# 10_RF_1.net
KiCad netlist of a schematic drawn in Altium Designer
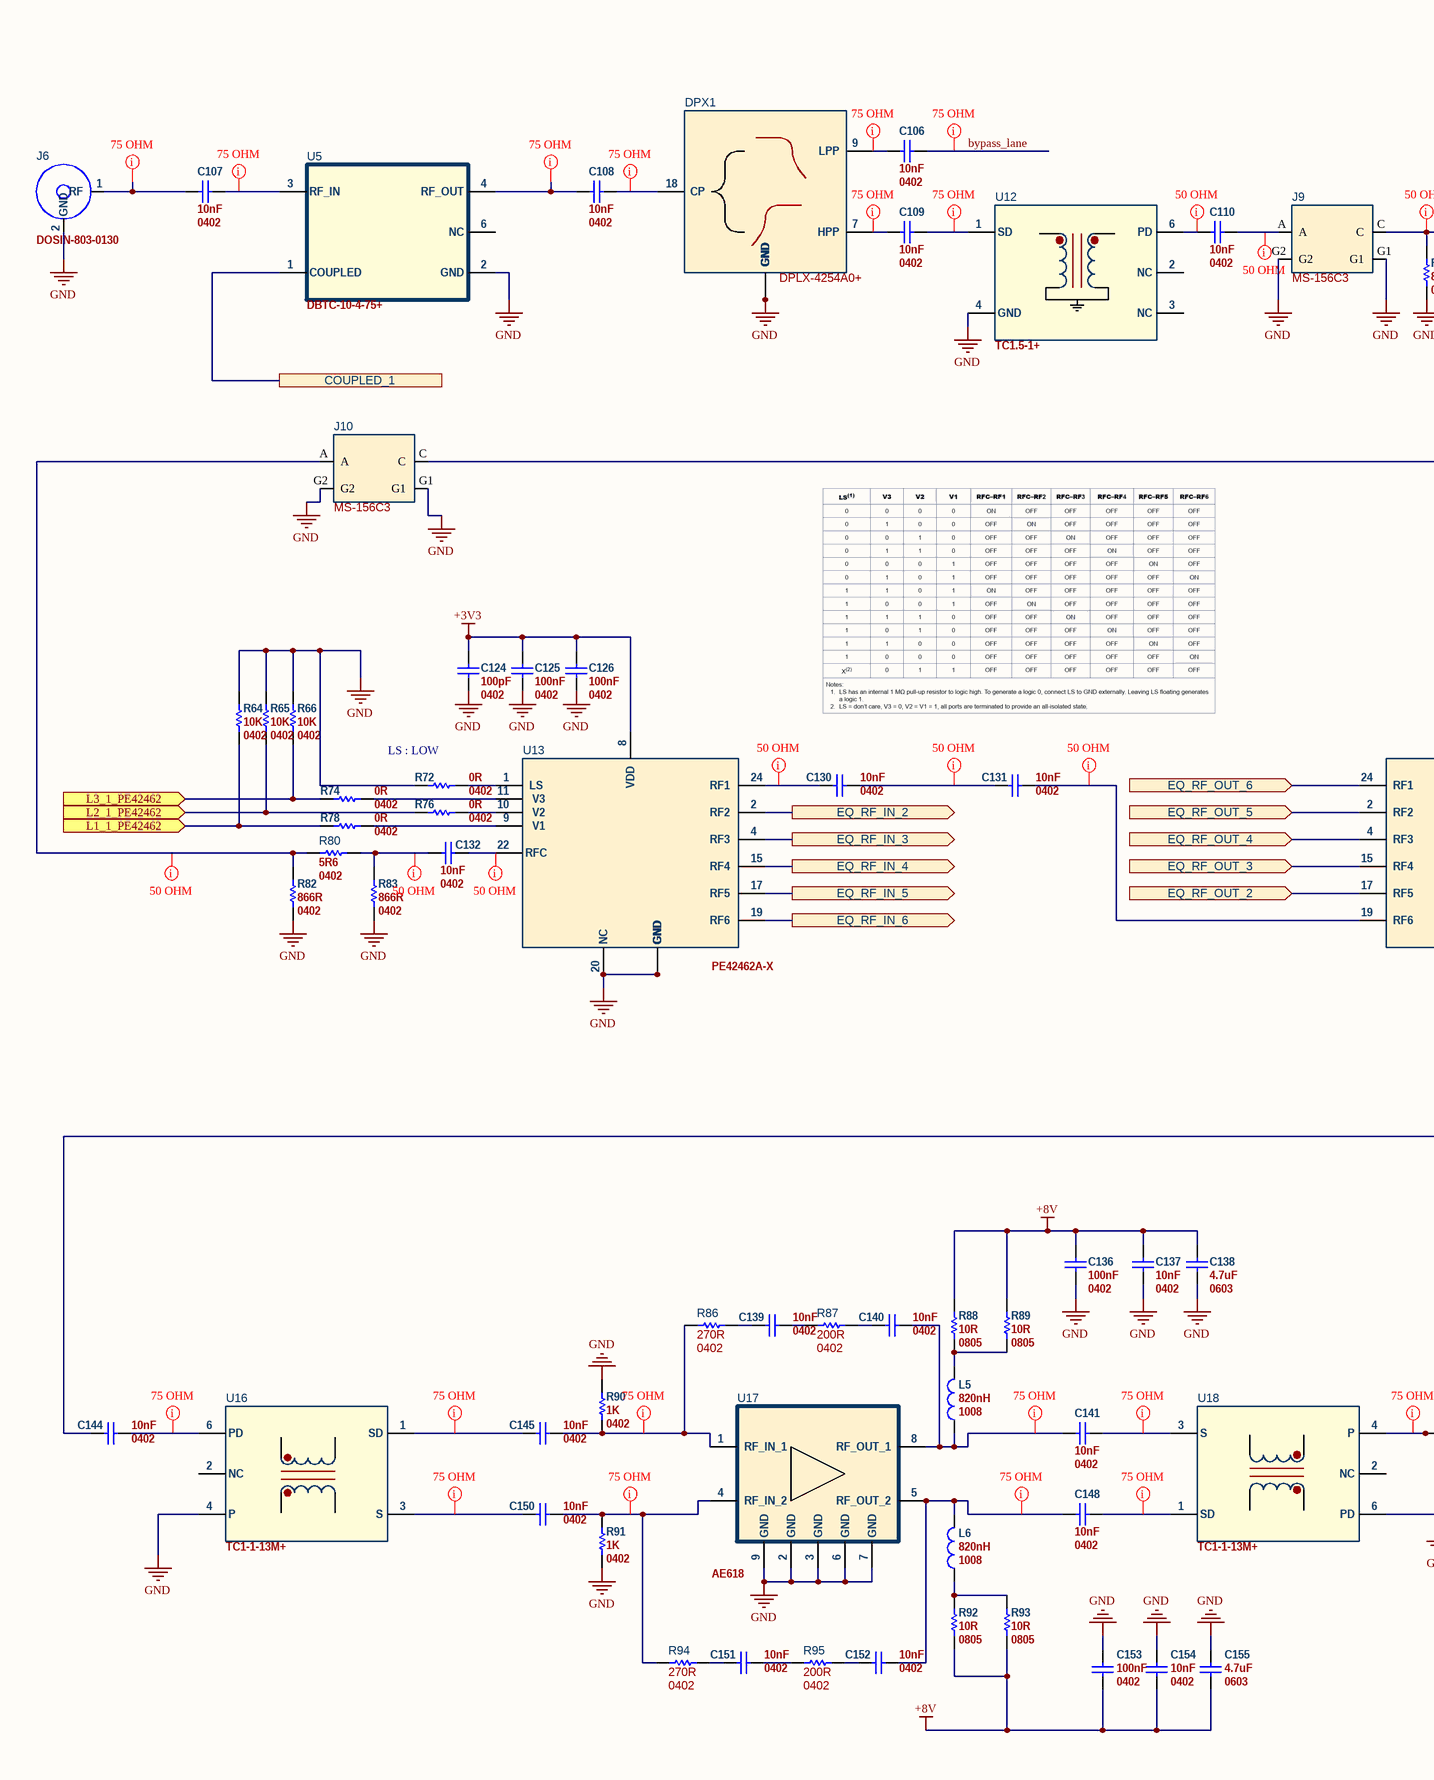
[diagram p0: 10_RF_1.SchDoc, left]
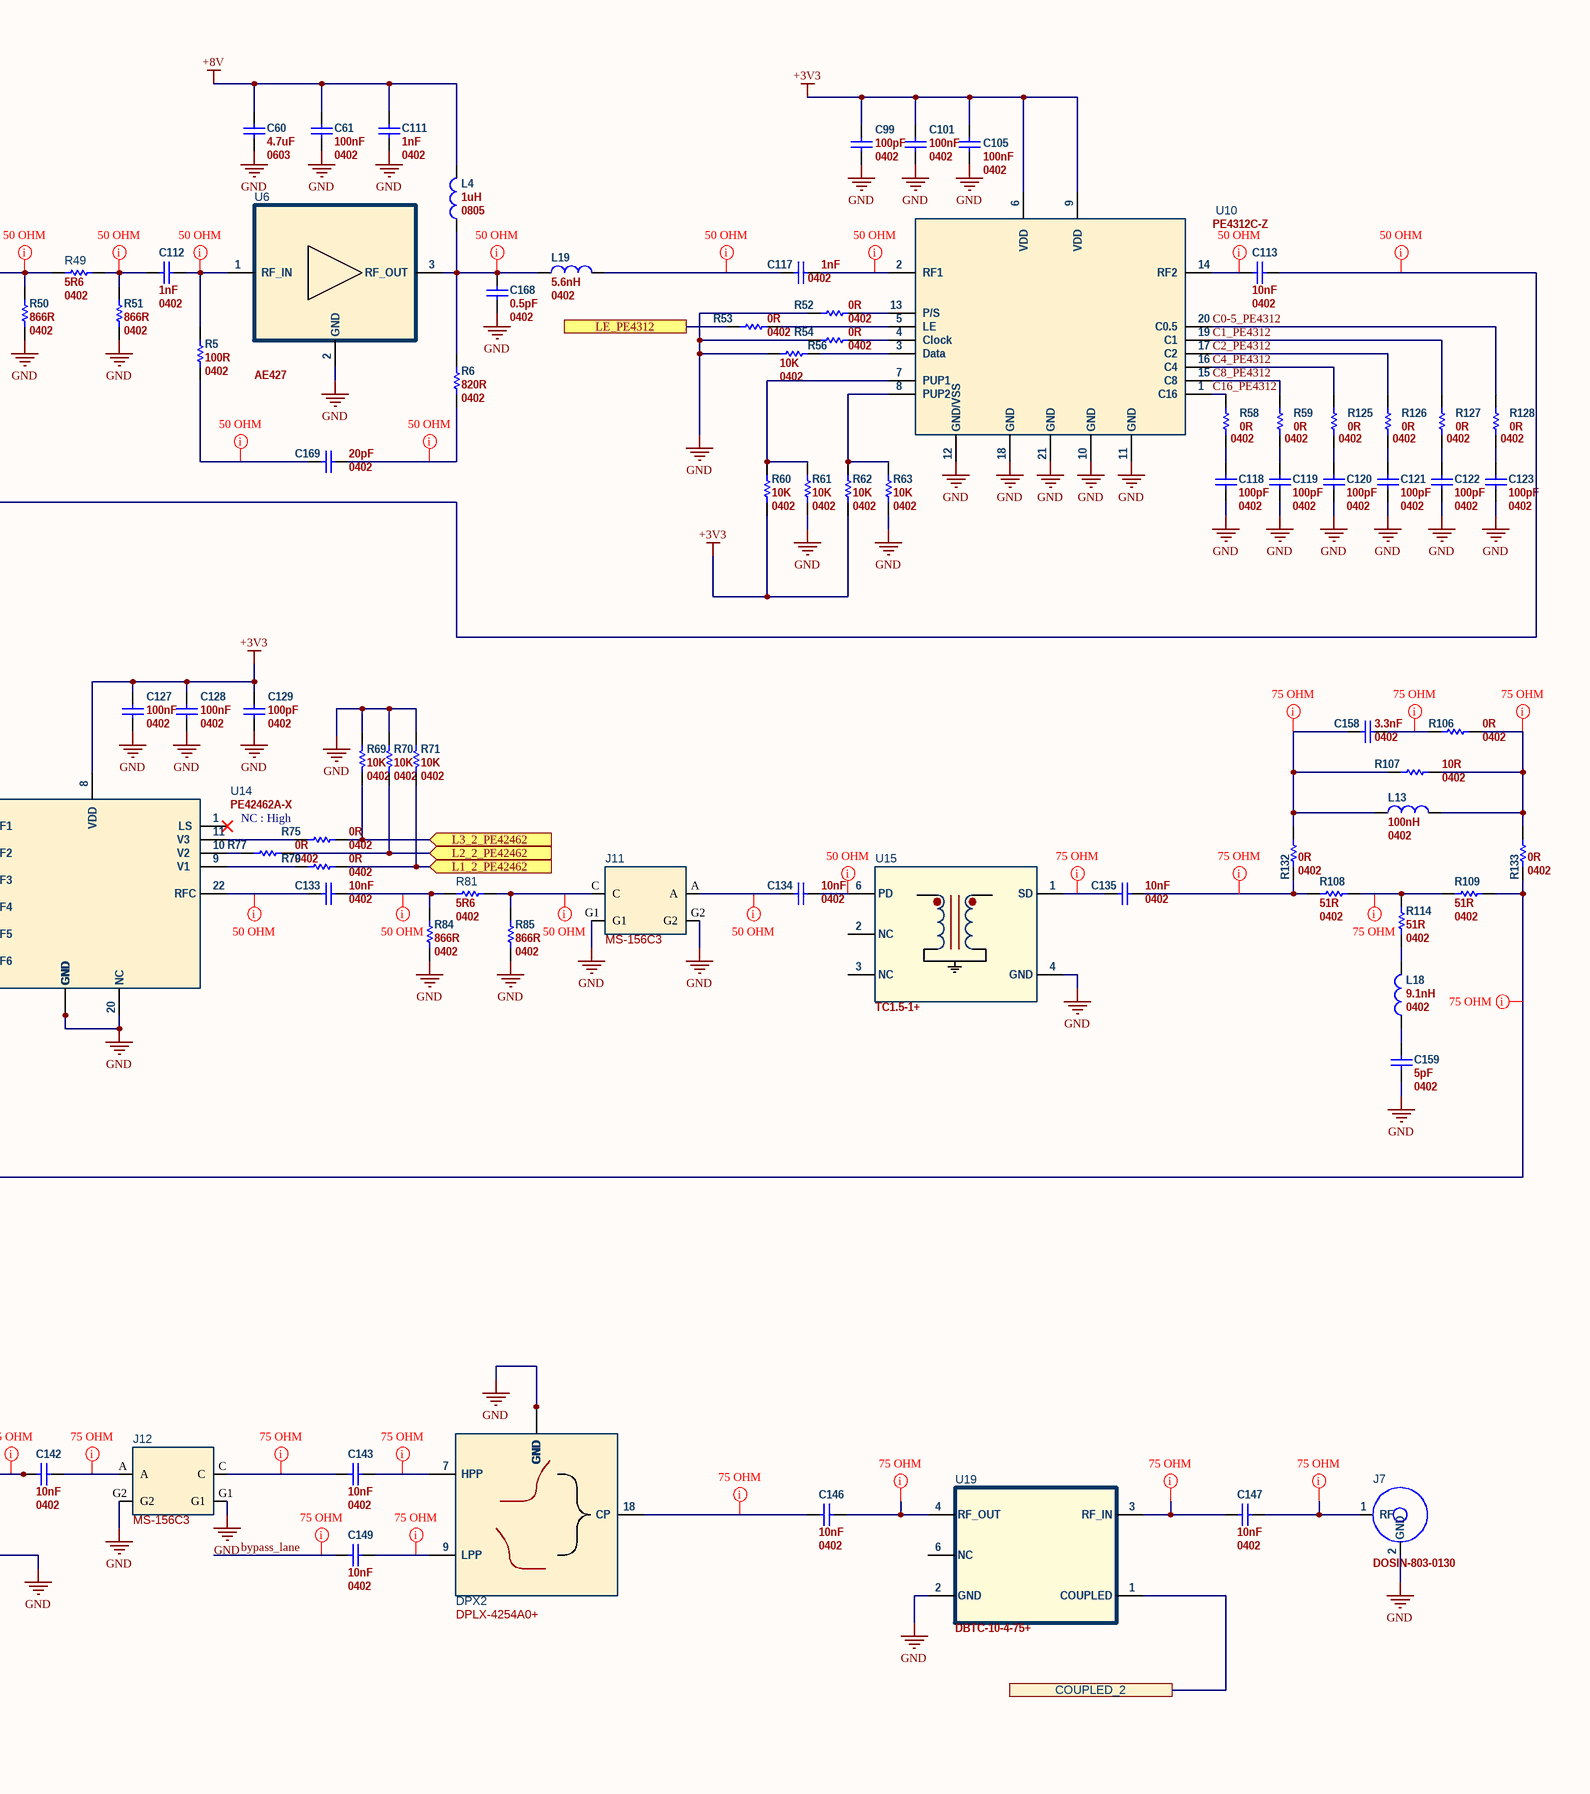
[diagram p1: 10_RF_1.SchDoc, right]

(export (version "E")
  (design (tool "Eeschema 10.0.6"))
  (components
    (comp (ref "C60")
      (value "4.7uF")
      (footprint "DISCRETE:CAP_0603_N")
      (description "CAP CER 4.7uF 16V X7R 0603 ±10%")
      (fields
        (field (name "TOLERANCE") "±10%")
        (field (name "PACKAGE") "0603")
        (field (name "Comment") "C 0603 16V X7R - 4.7uF")
        (field (name "COMPONENTLINK2URL") "D:\\SAVRONIK_SVN\\Donanım\\trunk\\ALTIUM\\Central Library\\Datasheets\\Capacitor\\GRM188Z71C475KE21-01A_Datasheet.pdf")
      )
      (libsource (lib "CAPACITOR") (part "C 0603 16V X7R - 4.7uF"))
    )
    (comp (ref "C61")
      (value "100nF")
      (footprint "DISCRETE:CAP_0402_N")
      (description "CAP CER 100nF 50V X7R 0402 ±10%")
      (fields
        (field (name "TOLERANCE") "±10%")
        (field (name "PACKAGE") "0402")
        (field (name "Comment") "C 0402 50V X7R - 100nF")
        (field (name "COMPONENTLINK2URL") "D:\\SAVRONIK_SVN\\Donanım\\trunk\\ALTIUM\\Central Library\\Datasheets\\Capacitor\\CGA2B3X7R1H104K050BB_Datasheet.pdf")
      )
      (libsource (lib "CAPACITOR") (part "C 0402 50V X7R - 100nF"))
    )
    (comp (ref "C99")
      (value "100pF")
      (footprint "DISCRETE:CAP_0402_N")
      (description "CAP CER 100pF 50V NP0 0402 ±1%")
      (fields
        (field (name "TOLERANCE") "±1%")
        (field (name "PACKAGE") "0402")
        (field (name "Comment") "C 0402 50V NP0 - 100pF")
      )
      (libsource (lib "CAPACITOR") (part "C 0402 50V NP0 - 100pF"))
    )
    (comp (ref "C101")
      (value "100nF")
      (footprint "DISCRETE:CAP_0402_N")
      (description "CAP CER 100nF 50V X7R 0402 ±10%")
      (fields
        (field (name "TOLERANCE") "±10%")
        (field (name "PACKAGE") "0402")
        (field (name "Comment") "C 0402 50V X7R - 100nF")
        (field (name "COMPONENTLINK2URL") "D:\\SAVRONIK_SVN\\Donanım\\trunk\\ALTIUM\\Central Library\\Datasheets\\Capacitor\\CGA2B3X7R1H104K050BB_Datasheet.pdf")
      )
      (libsource (lib "CAPACITOR") (part "C 0402 50V X7R - 100nF"))
    )
    (comp (ref "C105")
      (value "100nF")
      (footprint "DISCRETE:CAP_0402_N")
      (description "CAP CER 100nF 50V X7R 0402 ±10%")
      (fields
        (field (name "TOLERANCE") "±10%")
        (field (name "PACKAGE") "0402")
        (field (name "Comment") "C 0402 50V X7R - 100nF")
        (field (name "COMPONENTLINK2URL") "D:\\SAVRONIK_SVN\\Donanım\\trunk\\ALTIUM\\Central Library\\Datasheets\\Capacitor\\CGA2B3X7R1H104K050BB_Datasheet.pdf")
      )
      (libsource (lib "CAPACITOR") (part "C 0402 50V X7R - 100nF"))
    )
    (comp (ref "C106")
      (value "10nF")
      (footprint "DISCRETE:CAP_0402_N")
      (description "CAP CER 10nF 50V X7R 0402 ±10%")
      (fields
        (field (name "TOLERANCE") "±10%")
        (field (name "PACKAGE") "0402")
        (field (name "Comment") "C 0402 50V X7R - 10nF")
      )
      (libsource (lib "CAPACITOR") (part "C 0402 50V X7R - 10nF"))
    )
    (comp (ref "C107")
      (value "10nF")
      (footprint "DISCRETE:CAP_0402_N")
      (description "CAP CER 10nF 50V X7R 0402 ±10%")
      (fields
        (field (name "TOLERANCE") "±10%")
        (field (name "PACKAGE") "0402")
        (field (name "Comment") "C 0402 50V X7R - 10nF")
      )
      (libsource (lib "CAPACITOR") (part "C 0402 50V X7R - 10nF"))
    )
    (comp (ref "C108")
      (value "10nF")
      (footprint "DISCRETE:CAP_0402_N")
      (description "CAP CER 10nF 50V X7R 0402 ±10%")
      (fields
        (field (name "TOLERANCE") "±10%")
        (field (name "PACKAGE") "0402")
        (field (name "Comment") "C 0402 50V X7R - 10nF")
      )
      (libsource (lib "CAPACITOR") (part "C 0402 50V X7R - 10nF"))
    )
    (comp (ref "C109")
      (value "10nF")
      (footprint "DISCRETE:CAP_0402_N")
      (description "CAP CER 10nF 50V X7R 0402 ±10%")
      (fields
        (field (name "TOLERANCE") "±10%")
        (field (name "PACKAGE") "0402")
        (field (name "Comment") "C 0402 50V X7R - 10nF")
      )
      (libsource (lib "CAPACITOR") (part "C 0402 50V X7R - 10nF"))
    )
    (comp (ref "C110")
      (value "10nF")
      (footprint "DISCRETE:CAP_0402_N")
      (description "CAP CER 10nF 50V X7R 0402 ±10%")
      (fields
        (field (name "TOLERANCE") "±10%")
        (field (name "PACKAGE") "0402")
        (field (name "Comment") "C 0402 50V X7R - 10nF")
      )
      (libsource (lib "CAPACITOR") (part "C 0402 50V X7R - 10nF"))
    )
    (comp (ref "C111")
      (value "1nF")
      (footprint "DISCRETE:CAP_0402_N")
      (description "CAP CER 1nF 50V X7R 0402 ±10%")
      (fields
        (field (name "TOLERANCE") "±10%")
        (field (name "PACKAGE") "0402")
        (field (name "Comment") "C 0402 50V X7R - 1nF")
      )
      (libsource (lib "CAPACITOR") (part "C 0402 50V X7R - 1nF"))
    )
    (comp (ref "C112")
      (value "1nF")
      (footprint "DISCRETE:CAP_0402_N")
      (description "CAP CER 1nF 50V X7R 0402 ±10%")
      (fields
        (field (name "TOLERANCE") "±10%")
        (field (name "PACKAGE") "0402")
        (field (name "Comment") "C 0402 50V X7R - 1nF")
      )
      (libsource (lib "CAPACITOR") (part "C 0402 50V X7R - 1nF"))
    )
    (comp (ref "C113")
      (value "10nF")
      (footprint "DISCRETE:CAP_0402_N")
      (description "CAP CER 10nF 50V X7R 0402 ±10%")
      (fields
        (field (name "TOLERANCE") "±10%")
        (field (name "PACKAGE") "0402")
        (field (name "Comment") "C 0402 50V X7R - 10nF")
      )
      (libsource (lib "CAPACITOR") (part "C 0402 50V X7R - 10nF"))
    )
    (comp (ref "C117")
      (value "1nF")
      (footprint "DISCRETE:CAP_0402_N")
      (description "CAP CER 1nF 50V X7R 0402 ±10%")
      (fields
        (field (name "TOLERANCE") "±10%")
        (field (name "PACKAGE") "0402")
        (field (name "Comment") "C 0402 50V X7R - 1nF")
      )
      (libsource (lib "CAPACITOR") (part "C 0402 50V X7R - 1nF"))
    )
    (comp (ref "C118")
      (value "100pF")
      (footprint "DISCRETE:CAP_0402_N")
      (description "CAP CER 100pF 50V NP0 0402 ±1%")
      (fields
        (field (name "TOLERANCE") "±1%")
        (field (name "PACKAGE") "0402")
        (field (name "Comment") "C 0402 50V NP0 - 100pF")
      )
      (libsource (lib "CAPACITOR") (part "C 0402 50V NP0 - 100pF"))
    )
    (comp (ref "C119")
      (value "100pF")
      (footprint "DISCRETE:CAP_0402_N")
      (description "CAP CER 100pF 50V NP0 0402 ±1%")
      (fields
        (field (name "TOLERANCE") "±1%")
        (field (name "PACKAGE") "0402")
        (field (name "Comment") "C 0402 50V NP0 - 100pF")
      )
      (libsource (lib "CAPACITOR") (part "C 0402 50V NP0 - 100pF"))
    )
    (comp (ref "C120")
      (value "100pF")
      (footprint "DISCRETE:CAP_0402_N")
      (description "CAP CER 100pF 50V NP0 0402 ±1%")
      (fields
        (field (name "TOLERANCE") "±1%")
        (field (name "PACKAGE") "0402")
        (field (name "Comment") "C 0402 50V NP0 - 100pF")
      )
      (libsource (lib "CAPACITOR") (part "C 0402 50V NP0 - 100pF"))
    )
    (comp (ref "C121")
      (value "100pF")
      (footprint "DISCRETE:CAP_0402_N")
      (description "CAP CER 100pF 50V NP0 0402 ±1%")
      (fields
        (field (name "TOLERANCE") "±1%")
        (field (name "PACKAGE") "0402")
        (field (name "Comment") "C 0402 50V NP0 - 100pF")
      )
      (libsource (lib "CAPACITOR") (part "C 0402 50V NP0 - 100pF"))
    )
    (comp (ref "C122")
      (value "100pF")
      (footprint "DISCRETE:CAP_0402_N")
      (description "CAP CER 100pF 50V NP0 0402 ±1%")
      (fields
        (field (name "TOLERANCE") "±1%")
        (field (name "PACKAGE") "0402")
        (field (name "Comment") "C 0402 50V NP0 - 100pF")
      )
      (libsource (lib "CAPACITOR") (part "C 0402 50V NP0 - 100pF"))
    )
    (comp (ref "C123")
      (value "100pF")
      (footprint "DISCRETE:CAP_0402_N")
      (description "CAP CER 100pF 50V NP0 0402 ±1%")
      (fields
        (field (name "TOLERANCE") "±1%")
        (field (name "PACKAGE") "0402")
        (field (name "Comment") "C 0402 50V NP0 - 100pF")
      )
      (libsource (lib "CAPACITOR") (part "C 0402 50V NP0 - 100pF"))
    )
    (comp (ref "C124")
      (value "100pF")
      (footprint "DISCRETE:CAP_0402_N")
      (description "CAP CER 100pF 50V NP0 0402 ±1%")
      (fields
        (field (name "TOLERANCE") "±1%")
        (field (name "PACKAGE") "0402")
        (field (name "Comment") "C 0402 50V NP0 - 100pF")
      )
      (libsource (lib "CAPACITOR") (part "C 0402 50V NP0 - 100pF"))
    )
    (comp (ref "C125")
      (value "100nF")
      (footprint "DISCRETE:CAP_0402_N")
      (description "CAP CER 100nF 50V X7R 0402 ±10%")
      (fields
        (field (name "TOLERANCE") "±10%")
        (field (name "PACKAGE") "0402")
        (field (name "Comment") "C 0402 50V X7R - 100nF")
        (field (name "COMPONENTLINK2URL") "D:\\SAVRONIK_SVN\\Donanım\\trunk\\ALTIUM\\Central Library\\Datasheets\\Capacitor\\CGA2B3X7R1H104K050BB_Datasheet.pdf")
      )
      (libsource (lib "CAPACITOR") (part "C 0402 50V X7R - 100nF"))
    )
    (comp (ref "C126")
      (value "100nF")
      (footprint "DISCRETE:CAP_0402_N")
      (description "CAP CER 100nF 50V X7R 0402 ±10%")
      (fields
        (field (name "TOLERANCE") "±10%")
        (field (name "PACKAGE") "0402")
        (field (name "Comment") "C 0402 50V X7R - 100nF")
        (field (name "COMPONENTLINK2URL") "D:\\SAVRONIK_SVN\\Donanım\\trunk\\ALTIUM\\Central Library\\Datasheets\\Capacitor\\CGA2B3X7R1H104K050BB_Datasheet.pdf")
      )
      (libsource (lib "CAPACITOR") (part "C 0402 50V X7R - 100nF"))
    )
    (comp (ref "C127")
      (value "100nF")
      (footprint "DISCRETE:CAP_0402_N")
      (description "CAP CER 100nF 50V X7R 0402 ±10%")
      (fields
        (field (name "TOLERANCE") "±10%")
        (field (name "PACKAGE") "0402")
        (field (name "Comment") "C 0402 50V X7R - 100nF")
        (field (name "COMPONENTLINK2URL") "D:\\SAVRONIK_SVN\\Donanım\\trunk\\ALTIUM\\Central Library\\Datasheets\\Capacitor\\CGA2B3X7R1H104K050BB_Datasheet.pdf")
      )
      (libsource (lib "CAPACITOR") (part "C 0402 50V X7R - 100nF"))
    )
    (comp (ref "C128")
      (value "100nF")
      (footprint "DISCRETE:CAP_0402_N")
      (description "CAP CER 100nF 50V X7R 0402 ±10%")
      (fields
        (field (name "TOLERANCE") "±10%")
        (field (name "PACKAGE") "0402")
        (field (name "Comment") "C 0402 50V X7R - 100nF")
        (field (name "COMPONENTLINK2URL") "D:\\SAVRONIK_SVN\\Donanım\\trunk\\ALTIUM\\Central Library\\Datasheets\\Capacitor\\CGA2B3X7R1H104K050BB_Datasheet.pdf")
      )
      (libsource (lib "CAPACITOR") (part "C 0402 50V X7R - 100nF"))
    )
    (comp (ref "C129")
      (value "100pF")
      (footprint "DISCRETE:CAP_0402_N")
      (description "CAP CER 100pF 50V NP0 0402 ±1%")
      (fields
        (field (name "TOLERANCE") "±1%")
        (field (name "PACKAGE") "0402")
        (field (name "Comment") "C 0402 50V NP0 - 100pF")
      )
      (libsource (lib "CAPACITOR") (part "C 0402 50V NP0 - 100pF"))
    )
    (comp (ref "C130")
      (value "10nF")
      (footprint "DISCRETE:CAP_0402_N")
      (description "CAP CER 10nF 50V X7R 0402 ±10%")
      (fields
        (field (name "TOLERANCE") "±10%")
        (field (name "PACKAGE") "0402")
        (field (name "Comment") "C 0402 50V X7R - 10nF")
      )
      (libsource (lib "CAPACITOR") (part "C 0402 50V X7R - 10nF"))
    )
    (comp (ref "C131")
      (value "10nF")
      (footprint "DISCRETE:CAP_0402_N")
      (description "CAP CER 10nF 50V X7R 0402 ±10%")
      (fields
        (field (name "TOLERANCE") "±10%")
        (field (name "PACKAGE") "0402")
        (field (name "Comment") "C 0402 50V X7R - 10nF")
      )
      (libsource (lib "CAPACITOR") (part "C 0402 50V X7R - 10nF"))
    )
    (comp (ref "C132")
      (value "10nF")
      (footprint "DISCRETE:CAP_0402_N")
      (description "CAP CER 10nF 50V X7R 0402 ±10%")
      (fields
        (field (name "TOLERANCE") "±10%")
        (field (name "PACKAGE") "0402")
        (field (name "Comment") "C 0402 50V X7R - 10nF")
      )
      (libsource (lib "CAPACITOR") (part "C 0402 50V X7R - 10nF"))
    )
    (comp (ref "C133")
      (value "10nF")
      (footprint "DISCRETE:CAP_0402_N")
      (description "CAP CER 10nF 50V X7R 0402 ±10%")
      (fields
        (field (name "TOLERANCE") "±10%")
        (field (name "PACKAGE") "0402")
        (field (name "Comment") "C 0402 50V X7R - 10nF")
      )
      (libsource (lib "CAPACITOR") (part "C 0402 50V X7R - 10nF"))
    )
    (comp (ref "C134")
      (value "10nF")
      (footprint "DISCRETE:CAP_0402_N")
      (description "CAP CER 10nF 50V X7R 0402 ±10%")
      (fields
        (field (name "TOLERANCE") "±10%")
        (field (name "PACKAGE") "0402")
        (field (name "Comment") "C 0402 50V X7R - 10nF")
      )
      (libsource (lib "CAPACITOR") (part "C 0402 50V X7R - 10nF"))
    )
    (comp (ref "C135")
      (value "10nF")
      (footprint "DISCRETE:CAP_0402_N")
      (description "CAP CER 10nF 50V X7R 0402 ±10%")
      (fields
        (field (name "TOLERANCE") "±10%")
        (field (name "PACKAGE") "0402")
        (field (name "Comment") "C 0402 50V X7R - 10nF")
      )
      (libsource (lib "CAPACITOR") (part "C 0402 50V X7R - 10nF"))
    )
    (comp (ref "C136")
      (value "100nF")
      (footprint "DISCRETE:CAP_0402_N")
      (description "CAP CER 100nF 50V X7R 0402 ±10%")
      (fields
        (field (name "TOLERANCE") "±10%")
        (field (name "PACKAGE") "0402")
        (field (name "Comment") "C 0402 50V X7R - 100nF")
        (field (name "COMPONENTLINK2URL") "D:\\SAVRONIK_SVN\\Donanım\\trunk\\ALTIUM\\Central Library\\Datasheets\\Capacitor\\CGA2B3X7R1H104K050BB_Datasheet.pdf")
      )
      (libsource (lib "CAPACITOR") (part "C 0402 50V X7R - 100nF"))
    )
    (comp (ref "C137")
      (value "10nF")
      (footprint "DISCRETE:CAP_0402_N")
      (description "CAP CER 10nF 50V X7R 0402 ±10%")
      (fields
        (field (name "TOLERANCE") "±10%")
        (field (name "PACKAGE") "0402")
        (field (name "Comment") "C 0402 50V X7R - 10nF")
      )
      (libsource (lib "CAPACITOR") (part "C 0402 50V X7R - 10nF"))
    )
    (comp (ref "C138")
      (value "4.7uF")
      (footprint "DISCRETE:CAP_0603_N")
      (description "CAP CER 4.7uF 16V X7R 0603 ±10%")
      (fields
        (field (name "TOLERANCE") "±10%")
        (field (name "PACKAGE") "0603")
        (field (name "Comment") "C 0603 16V X7R - 4.7uF")
        (field (name "COMPONENTLINK2URL") "D:\\SAVRONIK_SVN\\Donanım\\trunk\\ALTIUM\\Central Library\\Datasheets\\Capacitor\\GRM188Z71C475KE21-01A_Datasheet.pdf")
      )
      (libsource (lib "CAPACITOR") (part "C 0603 16V X7R - 4.7uF"))
    )
    (comp (ref "C139")
      (value "10nF")
      (footprint "DISCRETE:CAP_0402_N")
      (description "CAP CER 10nF 50V X7R 0402 ±10%")
      (fields
        (field (name "TOLERANCE") "±10%")
        (field (name "PACKAGE") "0402")
        (field (name "Comment") "C 0402 50V X7R - 10nF")
      )
      (libsource (lib "CAPACITOR") (part "C 0402 50V X7R - 10nF"))
    )
    (comp (ref "C140")
      (value "10nF")
      (footprint "DISCRETE:CAP_0402_N")
      (description "CAP CER 10nF 50V X7R 0402 ±10%")
      (fields
        (field (name "TOLERANCE") "±10%")
        (field (name "PACKAGE") "0402")
        (field (name "Comment") "C 0402 50V X7R - 10nF")
      )
      (libsource (lib "CAPACITOR") (part "C 0402 50V X7R - 10nF"))
    )
    (comp (ref "C141")
      (value "10nF")
      (footprint "DISCRETE:CAP_0402_N")
      (description "CAP CER 10nF 50V X7R 0402 ±10%")
      (fields
        (field (name "TOLERANCE") "±10%")
        (field (name "PACKAGE") "0402")
        (field (name "Comment") "C 0402 50V X7R - 10nF")
      )
      (libsource (lib "CAPACITOR") (part "C 0402 50V X7R - 10nF"))
    )
    (comp (ref "C142")
      (value "10nF")
      (footprint "DISCRETE:CAP_0402_N")
      (description "CAP CER 10nF 50V X7R 0402 ±10%")
      (fields
        (field (name "TOLERANCE") "±10%")
        (field (name "PACKAGE") "0402")
        (field (name "Comment") "C 0402 50V X7R - 10nF")
      )
      (libsource (lib "CAPACITOR") (part "C 0402 50V X7R - 10nF"))
    )
    (comp (ref "C143")
      (value "10nF")
      (footprint "DISCRETE:CAP_0402_N")
      (description "CAP CER 10nF 50V X7R 0402 ±10%")
      (fields
        (field (name "TOLERANCE") "±10%")
        (field (name "PACKAGE") "0402")
        (field (name "Comment") "C 0402 50V X7R - 10nF")
      )
      (libsource (lib "CAPACITOR") (part "C 0402 50V X7R - 10nF"))
    )
    (comp (ref "C144")
      (value "10nF")
      (footprint "DISCRETE:CAP_0402_N")
      (description "CAP CER 10nF 50V X7R 0402 ±10%")
      (fields
        (field (name "TOLERANCE") "±10%")
        (field (name "PACKAGE") "0402")
        (field (name "Comment") "C 0402 50V X7R - 10nF")
      )
      (libsource (lib "CAPACITOR") (part "C 0402 50V X7R - 10nF"))
    )
    (comp (ref "C145")
      (value "10nF")
      (footprint "DISCRETE:CAP_0402_N")
      (description "CAP CER 10nF 50V X7R 0402 ±10%")
      (fields
        (field (name "TOLERANCE") "±10%")
        (field (name "PACKAGE") "0402")
        (field (name "Comment") "C 0402 50V X7R - 10nF")
      )
      (libsource (lib "CAPACITOR") (part "C 0402 50V X7R - 10nF"))
    )
    (comp (ref "C146")
      (value "10nF")
      (footprint "DISCRETE:CAP_0402_N")
      (description "CAP CER 10nF 50V X7R 0402 ±10%")
      (fields
        (field (name "TOLERANCE") "±10%")
        (field (name "PACKAGE") "0402")
        (field (name "Comment") "C 0402 50V X7R - 10nF")
      )
      (libsource (lib "CAPACITOR") (part "C 0402 50V X7R - 10nF"))
    )
    (comp (ref "C147")
      (value "10nF")
      (footprint "DISCRETE:CAP_0402_N")
      (description "CAP CER 10nF 50V X7R 0402 ±10%")
      (fields
        (field (name "TOLERANCE") "±10%")
        (field (name "PACKAGE") "0402")
        (field (name "Comment") "C 0402 50V X7R - 10nF")
      )
      (libsource (lib "CAPACITOR") (part "C 0402 50V X7R - 10nF"))
    )
    (comp (ref "C148")
      (value "10nF")
      (footprint "DISCRETE:CAP_0402_N")
      (description "CAP CER 10nF 50V X7R 0402 ±10%")
      (fields
        (field (name "TOLERANCE") "±10%")
        (field (name "PACKAGE") "0402")
        (field (name "Comment") "C 0402 50V X7R - 10nF")
      )
      (libsource (lib "CAPACITOR") (part "C 0402 50V X7R - 10nF"))
    )
    (comp (ref "C149")
      (value "10nF")
      (footprint "DISCRETE:CAP_0402_N")
      (description "CAP CER 10nF 50V X7R 0402 ±10%")
      (fields
        (field (name "TOLERANCE") "±10%")
        (field (name "PACKAGE") "0402")
        (field (name "Comment") "C 0402 50V X7R - 10nF")
      )
      (libsource (lib "CAPACITOR") (part "C 0402 50V X7R - 10nF"))
    )
    (comp (ref "C150")
      (value "10nF")
      (footprint "DISCRETE:CAP_0402_N")
      (description "CAP CER 10nF 50V X7R 0402 ±10%")
      (fields
        (field (name "TOLERANCE") "±10%")
        (field (name "PACKAGE") "0402")
        (field (name "Comment") "C 0402 50V X7R - 10nF")
      )
      (libsource (lib "CAPACITOR") (part "C 0402 50V X7R - 10nF"))
    )
    (comp (ref "C151")
      (value "10nF")
      (footprint "DISCRETE:CAP_0402_N")
      (description "CAP CER 10nF 50V X7R 0402 ±10%")
      (fields
        (field (name "TOLERANCE") "±10%")
        (field (name "PACKAGE") "0402")
        (field (name "Comment") "C 0402 50V X7R - 10nF")
      )
      (libsource (lib "CAPACITOR") (part "C 0402 50V X7R - 10nF"))
    )
    (comp (ref "C152")
      (value "10nF")
      (footprint "DISCRETE:CAP_0402_N")
      (description "CAP CER 10nF 50V X7R 0402 ±10%")
      (fields
        (field (name "TOLERANCE") "±10%")
        (field (name "PACKAGE") "0402")
        (field (name "Comment") "C 0402 50V X7R - 10nF")
      )
      (libsource (lib "CAPACITOR") (part "C 0402 50V X7R - 10nF"))
    )
    (comp (ref "C153")
      (value "100nF")
      (footprint "DISCRETE:CAP_0402_N")
      (description "CAP CER 100nF 50V X7R 0402 ±10%")
      (fields
        (field (name "TOLERANCE") "±10%")
        (field (name "PACKAGE") "0402")
        (field (name "Comment") "C 0402 50V X7R - 100nF")
        (field (name "COMPONENTLINK2URL") "D:\\SAVRONIK_SVN\\Donanım\\trunk\\ALTIUM\\Central Library\\Datasheets\\Capacitor\\CGA2B3X7R1H104K050BB_Datasheet.pdf")
      )
      (libsource (lib "CAPACITOR") (part "C 0402 50V X7R - 100nF"))
    )
    (comp (ref "C154")
      (value "10nF")
      (footprint "DISCRETE:CAP_0402_N")
      (description "CAP CER 10nF 50V X7R 0402 ±10%")
      (fields
        (field (name "TOLERANCE") "±10%")
        (field (name "PACKAGE") "0402")
        (field (name "Comment") "C 0402 50V X7R - 10nF")
      )
      (libsource (lib "CAPACITOR") (part "C 0402 50V X7R - 10nF"))
    )
    (comp (ref "C155")
      (value "4.7uF")
      (footprint "DISCRETE:CAP_0603_N")
      (description "CAP CER 4.7uF 16V X7R 0603 ±10%")
      (fields
        (field (name "TOLERANCE") "±10%")
        (field (name "PACKAGE") "0603")
        (field (name "Comment") "C 0603 16V X7R - 4.7uF")
        (field (name "COMPONENTLINK2URL") "D:\\SAVRONIK_SVN\\Donanım\\trunk\\ALTIUM\\Central Library\\Datasheets\\Capacitor\\GRM188Z71C475KE21-01A_Datasheet.pdf")
      )
      (libsource (lib "CAPACITOR") (part "C 0603 16V X7R - 4.7uF"))
    )
    (comp (ref "C158")
      (value "3.3nF")
      (footprint "DISCRETE:CAP_0402_N")
      (description "CAP CER 3.3nF 50V X7R 0402 ±5%")
      (fields
        (field (name "TOLERANCE") "±5%")
        (field (name "PACKAGE") "0402")
        (field (name "Comment") "C 0402 50V X7R - 3.3nF")
      )
      (libsource (lib "CAPACITOR") (part "C 0402 50V X7R - 3.3nF"))
    )
    (comp (ref "C159")
      (value "5pF")
      (footprint "DISCRETE:CAP_0402_N")
      (description "CAP CER 5pF 50V C0G/NP0 0402 ±0.1pF")
      (fields
        (field (name "TOLERANCE") "±0.1pF")
        (field (name "PACKAGE") "0402")
        (field (name "Comment") "C 0402 50V C0G/NP0 - 5pF")
      )
      (libsource (lib "CAPACITOR") (part "C 0402 50V C0G/NP0 - 5pF"))
    )
    (comp (ref "C168")
      (value "0.5pF")
      (footprint "DISCRETE:CAP_0402_N")
      (description "CAP CER 0.5pF 50V C0G/NP0 0402 ±0.1pF")
      (fields
        (field (name "TOLERANCE") "±0.1pF")
        (field (name "PACKAGE") "0402")
        (field (name "Comment") "C 0402 50V C0G/NP0 - 0.5pF")
      )
      (libsource (lib "CAPACITOR") (part "C 0402 50V C0G/NP0 - 0.5pF"))
    )
    (comp (ref "C169")
      (value "20pF")
      (footprint "DISCRETE:CAP_0402_N")
      (description "CAP CER 20pF 50V C0G/NP0 0402 ±1%")
      (fields
        (field (name "TOLERANCE") "±1%")
        (field (name "PACKAGE") "0402")
        (field (name "Comment") "C 0402 50V C0G/NP0 - 20pF")
      )
      (libsource (lib "CAPACITOR") (part "C 0402 50V C0G/NP0 - 20pF"))
    )
    (comp (ref "DPX1")
      (value "DPLX-4254A0+")
      (footprint "SMARTCATV:NU-1620")
      (description "RF DIPLEXER DC-42/54-1000 MHz NU1620 -40°C~85°C")
      (libsource (lib "SMARTCATV") (part "DPLX-4254A0+"))
    )
    (comp (ref "DPX2")
      (value "DPLX-4254A0+")
      (footprint "SMARTCATV:NU-1620")
      (description "RF DIPLEXER DC-42/54-1000 MHz NU1620 -40°C~85°C")
      (libsource (lib "") (part "DPLX-4254A0+_1"))
    )
    (comp (ref "J6")
      (value "DOSIN-803-0130")
      (footprint "SMARTCATV:1211-66137")
      (description "CONN F PLUG BOARD EDGE 75OHM -40°C~140°C")
      (libsource (lib "SMARTCATV") (part "DOSIN-803-0130"))
    )
    (comp (ref "J7")
      (value "DOSIN-803-0130")
      (footprint "SMARTCATV:1211-66137")
      (description "CONN F PLUG BOARD EDGE 75OHM -40°C~140°C")
      (libsource (lib "SMARTCATV") (part "DOSIN-803-0130"))
    )
    (comp (ref "J9")
      (value "MS-156C3")
      (footprint "HIROSE_MS-156C3")
      (description "COAX SW RF DIA 50OHM SMD -40°C~85°C")
      (libsource (lib "SMARTCATV") (part "MS-156C3"))
    )
    (comp (ref "J10")
      (value "MS-156C3")
      (footprint "HIROSE_MS-156C3")
      (description "COAX SW RF DIA 50OHM SMD -40°C~85°C")
      (libsource (lib "SMARTCATV") (part "MS-156C3"))
    )
    (comp (ref "J11")
      (value "MS-156C3")
      (footprint "HIROSE_MS-156C3")
      (description "COAX SW RF DIA 50OHM SMD -40°C~85°C")
      (libsource (lib "") (part "MS-156C3_1"))
    )
    (comp (ref "J12")
      (value "MS-156C3")
      (footprint "HIROSE_MS-156C3")
      (description "COAX SW RF DIA 50OHM SMD -40°C~85°C")
      (libsource (lib "SMARTCATV") (part "MS-156C3"))
    )
    (comp (ref "L4")
      (value "1uH")
      (footprint "IND_0806_LQH2MPN820MGRL")
      (description "IND 1uH 800mA 100mΩ DCR 0805 ±20% -55°C~125°C")
      (fields
        (field (name "TOLERANCE") "±20%")
        (field (name "PACKAGE") "0805")
        (field (name "Comment") "L 0805 800mA - 1uH")
      )
      (libsource (lib "SMARTCATV") (part "L 0805 800mA - 1uH"))
    )
    (comp (ref "L5")
      (value "820nH")
      (footprint "IND_1008_N")
      (description "IND 820nH 400mA Q:45@400MHz ±3% 1008 -55°C~125°C")
      (fields
        (field (name "TOLERANCE") "±5%")
        (field (name "PACKAGE") "1008")
        (field (name "Comment") "L 1008 400mA - 820nH")
      )
      (libsource (lib "SMARTCATV") (part "L 1008 400mA - 820nH"))
    )
    (comp (ref "L6")
      (value "820nH")
      (footprint "IND_1008_N")
      (description "IND 820nH 400mA Q:45@400MHz ±3% 1008 -55°C~125°C")
      (fields
        (field (name "TOLERANCE") "±5%")
        (field (name "PACKAGE") "1008")
        (field (name "Comment") "L 1008 400mA - 820nH")
      )
      (libsource (lib "SMARTCATV") (part "L 1008 400mA - 820nH"))
    )
    (comp (ref "L13")
      (value "100nH")
      (footprint "DISCRETE:IND_0402_N")
      (description "IND 100nH 310mA 1.57Ω DCR 0402 ±5% -40°C~125°C")
      (fields
        (field (name "TOLERANCE") "±5%")
        (field (name "PACKAGE") "0402")
        (field (name "Comment") "L 0402 310mA - 100nH")
        (field (name "COMPONENTLINK2URL") "D:\\SAVRONIK_SVN\\Donanım\\trunk\\ALTIUM\\Central Library\\Datasheets\\Inductor\\0402DC-R10XJRW_Datasheet.pdf")
      )
      (libsource (lib "INDUCTOR") (part "L 0402 310mA - 100nH"))
    )
    (comp (ref "L18")
      (value "9.1nH")
      (footprint "DISCRETE:IND_0402_N")
      (description "IND 9.1nH 1.6A 70mΩ DCR 0402 ±2% -40°C~125°C")
      (fields
        (field (name "TOLERANCE") "±2%")
        (field (name "PACKAGE") "0402")
        (field (name "Comment") "L 0402 1.6A - 9.1nH")
        (field (name "COMPONENTLINK2URL") "D:\\SAVRONIK_SVN\\Donanım\\trunk\\ALTIUM\\Central Library\\Datasheets\\Inductor\\0402DC-9N1XGRW_Datasheet.pdf")
      )
      (libsource (lib "INDUCTOR") (part "L 0402 1.6A - 9.1nH"))
    )
    (comp (ref "L19")
      (value "5.6nH")
      (footprint "DISCRETE:IND_0402_N")
      (description "IND 5.6nH 650mA 200mΩ DCR 0402 ±0.3nH -55°C~125°C")
      (fields
        (field (name "TOLERANCE") "±0.3nH")
        (field (name "PACKAGE") "0402")
        (field (name "Comment") "L 0402 650mA - 5.6nH")
        (field (name "COMPONENTLINK2URL") "D:\\SAVRONIK_SVN\\Donanım\\trunk\\ALTIUM\\Central Library\\Datasheets\\Inductor\\LQG15HS5N6S02D_Datasheet.pdf")
      )
      (libsource (lib "INDUCTOR") (part "L 0402 650mA - 5.6nH"))
    )
    (comp (ref "R5")
      (value "100R")
      (footprint "DISCRETE:RES_0402_N")
      (description "RES 100R 1/10W 0402 1%")
      (fields
        (field (name "TOLERANCE") "±1%")
        (field (name "PACKAGE") "0402")
        (field (name "Comment") "R 0402 1/10W 1% - 100R")
      )
      (libsource (lib "RESISTOR") (part "R 0402 1/10W 1% - 100R"))
    )
    (comp (ref "R6")
      (value "820R")
      (footprint "RES_0402_N")
      (description "RES 820R 1/10W 0402 1%")
      (fields
        (field (name "TOLERANCE") "±1%")
        (field (name "PACKAGE") "0402")
        (field (name "Comment") "R 0402 1/10W 1% - 820R")
      )
      (libsource (lib "SMARTCATV") (part "R 0402 1/10W 1% - 820R"))
    )
    (comp (ref "R49")
      (value "5R6")
      (footprint "RES_0402_N")
      (description "RES 5R6 1/10W 0402 1%")
      (fields
        (field (name "TOLERANCE") "±1%")
        (field (name "PACKAGE") "0402")
        (field (name "Comment") "R 0402 1/10W 1% - 5R6")
      )
      (libsource (lib "SMARTCATV") (part "R 0402 1/10W 1% - 5R6"))
    )
    (comp (ref "R50")
      (value "866R")
      (footprint "RES_0402_N")
      (description "RES 866R 1/10W 0402 1%")
      (fields
        (field (name "TOLERANCE") "±1%")
        (field (name "PACKAGE") "0402")
        (field (name "Comment") "R 0402 1/10W 1% - 866R")
      )
      (libsource (lib "SMARTCATV") (part "R 0402 1/10W 1% - 866R"))
    )
    (comp (ref "R51")
      (value "866R")
      (footprint "RES_0402_N")
      (description "RES 866R 1/10W 0402 1%")
      (fields
        (field (name "TOLERANCE") "±1%")
        (field (name "PACKAGE") "0402")
        (field (name "Comment") "R 0402 1/10W 1% - 866R")
      )
      (libsource (lib "SMARTCATV") (part "R 0402 1/10W 1% - 866R"))
    )
    (comp (ref "R52")
      (value "0R")
      (footprint "DISCRETE:RES_0402_N")
      (description "RES 0R 1/10W 0402")
      (fields
        (field (name "PACKAGE") "0402")
        (field (name "Comment") "R 0402 1/10W - 0R")
        (field (name "COMPONENTLINK2URL") "D:\\SAVRONIK_SVN\\Donanım\\trunk\\ALTIUM\\Central Library\\Datasheets\\Resistor\\ERJ-2GE0R00X_Datasheet.pdf")
      )
      (libsource (lib "RESISTOR") (part "R 0402 1/10W - 0R"))
    )
    (comp (ref "R53")
      (value "0R")
      (footprint "DISCRETE:RES_0402_N")
      (description "RES 0R 1/10W 0402")
      (fields
        (field (name "PACKAGE") "0402")
        (field (name "Comment") "R 0402 1/10W - 0R")
        (field (name "COMPONENTLINK2URL") "D:\\SAVRONIK_SVN\\Donanım\\trunk\\ALTIUM\\Central Library\\Datasheets\\Resistor\\ERJ-2GE0R00X_Datasheet.pdf")
      )
      (libsource (lib "RESISTOR") (part "R 0402 1/10W - 0R"))
    )
    (comp (ref "R54")
      (value "0R")
      (footprint "DISCRETE:RES_0402_N")
      (description "RES 0R 1/10W 0402")
      (fields
        (field (name "PACKAGE") "0402")
        (field (name "Comment") "R 0402 1/10W - 0R")
        (field (name "COMPONENTLINK2URL") "D:\\SAVRONIK_SVN\\Donanım\\trunk\\ALTIUM\\Central Library\\Datasheets\\Resistor\\ERJ-2GE0R00X_Datasheet.pdf")
      )
      (libsource (lib "RESISTOR") (part "R 0402 1/10W - 0R"))
    )
    (comp (ref "R56")
      (value "10K")
      (footprint "DISCRETE:RES_0402_N")
      (description "RES 10K 1/10W 0402 1%")
      (fields
        (field (name "TOLERANCE") "±1%")
        (field (name "PACKAGE") "0402")
        (field (name "Comment") "R 0402 1/10W 1% - 10K")
      )
      (libsource (lib "RESISTOR") (part "R 0402 1/10W 1% - 10K"))
    )
    (comp (ref "R58")
      (value "0R")
      (footprint "DISCRETE:RES_0402_N")
      (description "RES 0R 1/10W 0402")
      (fields
        (field (name "PACKAGE") "0402")
        (field (name "Comment") "R 0402 1/10W - 0R")
        (field (name "COMPONENTLINK2URL") "D:\\SAVRONIK_SVN\\Donanım\\trunk\\ALTIUM\\Central Library\\Datasheets\\Resistor\\ERJ-2GE0R00X_Datasheet.pdf")
      )
      (libsource (lib "RESISTOR") (part "R 0402 1/10W - 0R"))
    )
    (comp (ref "R59")
      (value "0R")
      (footprint "DISCRETE:RES_0402_N")
      (description "RES 0R 1/10W 0402")
      (fields
        (field (name "PACKAGE") "0402")
        (field (name "Comment") "R 0402 1/10W - 0R")
        (field (name "COMPONENTLINK2URL") "D:\\SAVRONIK_SVN\\Donanım\\trunk\\ALTIUM\\Central Library\\Datasheets\\Resistor\\ERJ-2GE0R00X_Datasheet.pdf")
      )
      (libsource (lib "RESISTOR") (part "R 0402 1/10W - 0R"))
    )
    (comp (ref "R60")
      (value "10K")
      (footprint "DISCRETE:RES_0402_N")
      (description "RES 10K 1/10W 0402 1%")
      (fields
        (field (name "TOLERANCE") "±1%")
        (field (name "PACKAGE") "0402")
        (field (name "Comment") "R 0402 1/10W 1% - 10K")
      )
      (libsource (lib "RESISTOR") (part "R 0402 1/10W 1% - 10K"))
    )
    (comp (ref "R61")
      (value "10K")
      (footprint "DISCRETE:RES_0402_N")
      (description "RES 10K 1/10W 0402 1%")
      (fields
        (field (name "TOLERANCE") "±1%")
        (field (name "PACKAGE") "0402")
        (field (name "Comment") "R 0402 1/10W 1% - 10K")
      )
      (libsource (lib "RESISTOR") (part "R 0402 1/10W 1% - 10K"))
    )
    (comp (ref "R62")
      (value "10K")
      (footprint "DISCRETE:RES_0402_N")
      (description "RES 10K 1/10W 0402 1%")
      (fields
        (field (name "TOLERANCE") "±1%")
        (field (name "PACKAGE") "0402")
        (field (name "Comment") "R 0402 1/10W 1% - 10K")
      )
      (libsource (lib "RESISTOR") (part "R 0402 1/10W 1% - 10K"))
    )
    (comp (ref "R63")
      (value "10K")
      (footprint "DISCRETE:RES_0402_N")
      (description "RES 10K 1/10W 0402 1%")
      (fields
        (field (name "TOLERANCE") "±1%")
        (field (name "PACKAGE") "0402")
        (field (name "Comment") "R 0402 1/10W 1% - 10K")
      )
      (libsource (lib "RESISTOR") (part "R 0402 1/10W 1% - 10K"))
    )
    (comp (ref "R64")
      (value "10K")
      (footprint "DISCRETE:RES_0402_N")
      (description "RES 10K 1/10W 0402 1%")
      (fields
        (field (name "TOLERANCE") "±1%")
        (field (name "PACKAGE") "0402")
        (field (name "Comment") "R 0402 1/10W 1% - 10K")
      )
      (libsource (lib "RESISTOR") (part "R 0402 1/10W 1% - 10K"))
    )
    (comp (ref "R65")
      (value "10K")
      (footprint "DISCRETE:RES_0402_N")
      (description "RES 10K 1/10W 0402 1%")
      (fields
        (field (name "TOLERANCE") "±1%")
        (field (name "PACKAGE") "0402")
        (field (name "Comment") "R 0402 1/10W 1% - 10K")
      )
      (libsource (lib "RESISTOR") (part "R 0402 1/10W 1% - 10K"))
    )
    (comp (ref "R66")
      (value "10K")
      (footprint "DISCRETE:RES_0402_N")
      (description "RES 10K 1/10W 0402 1%")
      (fields
        (field (name "TOLERANCE") "±1%")
        (field (name "PACKAGE") "0402")
        (field (name "Comment") "R 0402 1/10W 1% - 10K")
      )
      (libsource (lib "RESISTOR") (part "R 0402 1/10W 1% - 10K"))
    )
    (comp (ref "R69")
      (value "10K")
      (footprint "DISCRETE:RES_0402_N")
      (description "RES 10K 1/10W 0402 1%")
      (fields
        (field (name "TOLERANCE") "±1%")
        (field (name "PACKAGE") "0402")
        (field (name "Comment") "R 0402 1/10W 1% - 10K")
      )
      (libsource (lib "RESISTOR") (part "R 0402 1/10W 1% - 10K"))
    )
    (comp (ref "R70")
      (value "10K")
      (footprint "DISCRETE:RES_0402_N")
      (description "RES 10K 1/10W 0402 1%")
      (fields
        (field (name "TOLERANCE") "±1%")
        (field (name "PACKAGE") "0402")
        (field (name "Comment") "R 0402 1/10W 1% - 10K")
      )
      (libsource (lib "RESISTOR") (part "R 0402 1/10W 1% - 10K"))
    )
    (comp (ref "R71")
      (value "10K")
      (footprint "DISCRETE:RES_0402_N")
      (description "RES 10K 1/10W 0402 1%")
      (fields
        (field (name "TOLERANCE") "±1%")
        (field (name "PACKAGE") "0402")
        (field (name "Comment") "R 0402 1/10W 1% - 10K")
      )
      (libsource (lib "RESISTOR") (part "R 0402 1/10W 1% - 10K"))
    )
    (comp (ref "R72")
      (value "0R")
      (footprint "DISCRETE:RES_0402_N")
      (description "RES 0R 1/10W 0402")
      (fields
        (field (name "PACKAGE") "0402")
        (field (name "Comment") "R 0402 1/10W - 0R")
        (field (name "COMPONENTLINK2URL") "D:\\SAVRONIK_SVN\\Donanım\\trunk\\ALTIUM\\Central Library\\Datasheets\\Resistor\\ERJ-2GE0R00X_Datasheet.pdf")
      )
      (libsource (lib "RESISTOR") (part "R 0402 1/10W - 0R"))
    )
    (comp (ref "R74")
      (value "0R")
      (footprint "DISCRETE:RES_0402_N")
      (description "RES 0R 1/10W 0402")
      (fields
        (field (name "PACKAGE") "0402")
        (field (name "Comment") "R 0402 1/10W - 0R")
        (field (name "COMPONENTLINK2URL") "D:\\SAVRONIK_SVN\\Donanım\\trunk\\ALTIUM\\Central Library\\Datasheets\\Resistor\\ERJ-2GE0R00X_Datasheet.pdf")
      )
      (libsource (lib "RESISTOR") (part "R 0402 1/10W - 0R"))
    )
    (comp (ref "R75")
      (value "0R")
      (footprint "DISCRETE:RES_0402_N")
      (description "RES 0R 1/10W 0402")
      (fields
        (field (name "PACKAGE") "0402")
        (field (name "Comment") "R 0402 1/10W - 0R")
        (field (name "COMPONENTLINK2URL") "D:\\SAVRONIK_SVN\\Donanım\\trunk\\ALTIUM\\Central Library\\Datasheets\\Resistor\\ERJ-2GE0R00X_Datasheet.pdf")
      )
      (libsource (lib "RESISTOR") (part "R 0402 1/10W - 0R"))
    )
    (comp (ref "R76")
      (value "0R")
      (footprint "DISCRETE:RES_0402_N")
      (description "RES 0R 1/10W 0402")
      (fields
        (field (name "PACKAGE") "0402")
        (field (name "Comment") "R 0402 1/10W - 0R")
        (field (name "COMPONENTLINK2URL") "D:\\SAVRONIK_SVN\\Donanım\\trunk\\ALTIUM\\Central Library\\Datasheets\\Resistor\\ERJ-2GE0R00X_Datasheet.pdf")
      )
      (libsource (lib "RESISTOR") (part "R 0402 1/10W - 0R"))
    )
    (comp (ref "R77")
      (value "0R")
      (footprint "DISCRETE:RES_0402_N")
      (description "RES 0R 1/10W 0402")
      (fields
        (field (name "PACKAGE") "0402")
        (field (name "Comment") "R 0402 1/10W - 0R")
        (field (name "COMPONENTLINK2URL") "D:\\SAVRONIK_SVN\\Donanım\\trunk\\ALTIUM\\Central Library\\Datasheets\\Resistor\\ERJ-2GE0R00X_Datasheet.pdf")
      )
      (libsource (lib "RESISTOR") (part "R 0402 1/10W - 0R"))
    )
    (comp (ref "R78")
      (value "0R")
      (footprint "DISCRETE:RES_0402_N")
      (description "RES 0R 1/10W 0402")
      (fields
        (field (name "PACKAGE") "0402")
        (field (name "Comment") "R 0402 1/10W - 0R")
        (field (name "COMPONENTLINK2URL") "D:\\SAVRONIK_SVN\\Donanım\\trunk\\ALTIUM\\Central Library\\Datasheets\\Resistor\\ERJ-2GE0R00X_Datasheet.pdf")
      )
      (libsource (lib "RESISTOR") (part "R 0402 1/10W - 0R"))
    )
    (comp (ref "R79")
      (value "0R")
      (footprint "DISCRETE:RES_0402_N")
      (description "RES 0R 1/10W 0402")
      (fields
        (field (name "PACKAGE") "0402")
        (field (name "Comment") "R 0402 1/10W - 0R")
        (field (name "COMPONENTLINK2URL") "D:\\SAVRONIK_SVN\\Donanım\\trunk\\ALTIUM\\Central Library\\Datasheets\\Resistor\\ERJ-2GE0R00X_Datasheet.pdf")
      )
      (libsource (lib "RESISTOR") (part "R 0402 1/10W - 0R"))
    )
    (comp (ref "R80")
      (value "5R6")
      (footprint "RES_0402_N")
      (description "RES 5R6 1/10W 0402 1%")
      (fields
        (field (name "TOLERANCE") "±1%")
        (field (name "PACKAGE") "0402")
        (field (name "Comment") "R 0402 1/10W 1% - 5R6")
      )
      (libsource (lib "SMARTCATV") (part "R 0402 1/10W 1% - 5R6"))
    )
    (comp (ref "R81")
      (value "5R6")
      (footprint "RES_0402_N")
      (description "RES 5R6 1/10W 0402 1%")
      (fields
        (field (name "TOLERANCE") "±1%")
        (field (name "PACKAGE") "0402")
        (field (name "Comment") "R 0402 1/10W 1% - 5R6")
      )
      (libsource (lib "SMARTCATV") (part "R 0402 1/10W 1% - 5R6"))
    )
    (comp (ref "R82")
      (value "866R")
      (footprint "RES_0402_N")
      (description "RES 866R 1/10W 0402 1%")
      (fields
        (field (name "TOLERANCE") "±1%")
        (field (name "PACKAGE") "0402")
        (field (name "Comment") "R 0402 1/10W 1% - 866R")
      )
      (libsource (lib "SMARTCATV") (part "R 0402 1/10W 1% - 866R"))
    )
    (comp (ref "R83")
      (value "866R")
      (footprint "RES_0402_N")
      (description "RES 866R 1/10W 0402 1%")
      (fields
        (field (name "TOLERANCE") "±1%")
        (field (name "PACKAGE") "0402")
        (field (name "Comment") "R 0402 1/10W 1% - 866R")
      )
      (libsource (lib "SMARTCATV") (part "R 0402 1/10W 1% - 866R"))
    )
    (comp (ref "R84")
      (value "866R")
      (footprint "RES_0402_N")
      (description "RES 866R 1/10W 0402 1%")
      (fields
        (field (name "TOLERANCE") "±1%")
        (field (name "PACKAGE") "0402")
        (field (name "Comment") "R 0402 1/10W 1% - 866R")
      )
      (libsource (lib "SMARTCATV") (part "R 0402 1/10W 1% - 866R"))
    )
    (comp (ref "R85")
      (value "866R")
      (footprint "RES_0402_N")
      (description "RES 866R 1/10W 0402 1%")
      (fields
        (field (name "TOLERANCE") "±1%")
        (field (name "PACKAGE") "0402")
        (field (name "Comment") "R 0402 1/10W 1% - 866R")
      )
      (libsource (lib "SMARTCATV") (part "R 0402 1/10W 1% - 866R"))
    )
    (comp (ref "R86")
      (value "270R")
      (footprint "RES_0402_N")
      (description "RES 270R 1/10W 0402 1%")
      (fields
        (field (name "TOLERANCE") "±1%")
        (field (name "PACKAGE") "0402")
        (field (name "Comment") "R 0402 1/10W 1% - 270R")
      )
      (libsource (lib "SMARTCATV") (part "R 0402 1/10W 1% - 270R"))
    )
    (comp (ref "R87")
      (value "200R")
      (footprint "RES_0402_N")
      (description "RES 200R 1/10W 0402 1%")
      (fields
        (field (name "TOLERANCE") "±1%")
        (field (name "PACKAGE") "0402")
        (field (name "Comment") "R 0402 1/10W 1% - 200R")
      )
      (libsource (lib "SMARTCATV") (part "R 0402 1/10W 1% - 200R"))
    )
    (comp (ref "R88")
      (value "10R")
      (footprint "RES_0805_N")
      (description "RES 10R 1/2W 0805 1%")
      (fields
        (field (name "TOLERANCE") "±1%")
        (field (name "PACKAGE") "0805")
        (field (name "Comment") "R 0805 1/2W 1% - 10R")
      )
      (libsource (lib "SMARTCATV") (part "R 0805 1/2W 1% - 10R"))
    )
    (comp (ref "R89")
      (value "10R")
      (footprint "RES_0805_N")
      (description "RES 10R 1/2W 0805 1%")
      (fields
        (field (name "TOLERANCE") "±1%")
        (field (name "PACKAGE") "0805")
        (field (name "Comment") "R 0805 1/2W 1% - 10R")
      )
      (libsource (lib "SMARTCATV") (part "R 0805 1/2W 1% - 10R"))
    )
    (comp (ref "R90")
      (value "1K")
      (footprint "DISCRETE:RES_0402_N")
      (description "RES 1K 1/10W 0402 1%")
      (fields
        (field (name "TOLERANCE") "±1%")
        (field (name "PACKAGE") "0402")
        (field (name "Comment") "R 0402 1/10W 1% - 1K")
      )
      (libsource (lib "RESISTOR") (part "R 0402 1/10W 1% - 1K"))
    )
    (comp (ref "R91")
      (value "1K")
      (footprint "DISCRETE:RES_0402_N")
      (description "RES 1K 1/10W 0402 1%")
      (fields
        (field (name "TOLERANCE") "±1%")
        (field (name "PACKAGE") "0402")
        (field (name "Comment") "R 0402 1/10W 1% - 1K")
      )
      (libsource (lib "RESISTOR") (part "R 0402 1/10W 1% - 1K"))
    )
    (comp (ref "R92")
      (value "10R")
      (footprint "RES_0805_N")
      (description "RES 10R 1/2W 0805 1%")
      (fields
        (field (name "TOLERANCE") "±1%")
        (field (name "PACKAGE") "0805")
        (field (name "Comment") "R 0805 1/2W 1% - 10R")
      )
      (libsource (lib "SMARTCATV") (part "R 0805 1/2W 1% - 10R"))
    )
    (comp (ref "R93")
      (value "10R")
      (footprint "RES_0805_N")
      (description "RES 10R 1/2W 0805 1%")
      (fields
        (field (name "TOLERANCE") "±1%")
        (field (name "PACKAGE") "0805")
        (field (name "Comment") "R 0805 1/2W 1% - 10R")
      )
      (libsource (lib "SMARTCATV") (part "R 0805 1/2W 1% - 10R"))
    )
    (comp (ref "R94")
      (value "270R")
      (footprint "RES_0402_N")
      (description "RES 270R 1/10W 0402 1%")
      (fields
        (field (name "TOLERANCE") "±1%")
        (field (name "PACKAGE") "0402")
        (field (name "Comment") "R 0402 1/10W 1% - 270R")
      )
      (libsource (lib "SMARTCATV") (part "R 0402 1/10W 1% - 270R"))
    )
    (comp (ref "R95")
      (value "200R")
      (footprint "RES_0402_N")
      (description "RES 200R 1/10W 0402 1%")
      (fields
        (field (name "TOLERANCE") "±1%")
        (field (name "PACKAGE") "0402")
        (field (name "Comment") "R 0402 1/10W 1% - 200R")
      )
      (libsource (lib "SMARTCATV") (part "R 0402 1/10W 1% - 200R"))
    )
    (comp (ref "R106")
      (value "0R")
      (footprint "DISCRETE:RES_0402_N")
      (description "RES 0R 1/10W 0402")
      (fields (field (name "PACKAGE") "0402") (field (name "Comment") "R 0402 1/10W - 0R"))
      (libsource (lib "RESISTOR") (part "R 0402 1/10W - 0R"))
    )
    (comp (ref "R107")
      (value "10R")
      (footprint "DISCRETE:RES_0402_N")
      (description "RES 10R 1/10W 0402 1%")
      (fields
        (field (name "TOLERANCE") "±1%")
        (field (name "PACKAGE") "0402")
        (field (name "Comment") "R 0402 1/10W 1% - 10R")
      )
      (libsource (lib "RESISTOR") (part "R 0402 1/10W 1% - 10R"))
    )
    (comp (ref "R108")
      (value "51R")
      (footprint "RES_0402_N")
      (description "RES 51R 1/10W 0402 1%")
      (fields
        (field (name "TOLERANCE") "±1%")
        (field (name "PACKAGE") "0402")
        (field (name "Comment") "R 0402 1/10W 1% - 51R")
      )
      (libsource (lib "SMARTCATV") (part "R 0402 1/10W 1% - 51R"))
    )
    (comp (ref "R109")
      (value "51R")
      (footprint "RES_0402_N")
      (description "RES 51R 1/10W 0402 1%")
      (fields
        (field (name "TOLERANCE") "±1%")
        (field (name "PACKAGE") "0402")
        (field (name "Comment") "R 0402 1/10W 1% - 51R")
      )
      (libsource (lib "SMARTCATV") (part "R 0402 1/10W 1% - 51R"))
    )
    (comp (ref "R114")
      (value "51R")
      (footprint "RES_0402_N")
      (description "RES 51R 1/10W 0402 1%")
      (fields
        (field (name "TOLERANCE") "±1%")
        (field (name "PACKAGE") "0402")
        (field (name "Comment") "R 0402 1/10W 1% - 51R")
      )
      (libsource (lib "SMARTCATV") (part "R 0402 1/10W 1% - 51R"))
    )
    (comp (ref "R125")
      (value "0R")
      (footprint "DISCRETE:RES_0402_N")
      (description "RES 0R 1/10W 0402")
      (fields
        (field (name "PACKAGE") "0402")
        (field (name "Comment") "R 0402 1/10W - 0R")
        (field (name "COMPONENTLINK2URL") "D:\\SAVRONIK_SVN\\Donanım\\trunk\\ALTIUM\\Central Library\\Datasheets\\Resistor\\ERJ-2GE0R00X_Datasheet.pdf")
      )
      (libsource (lib "RESISTOR") (part "R 0402 1/10W - 0R"))
    )
    (comp (ref "R126")
      (value "0R")
      (footprint "DISCRETE:RES_0402_N")
      (description "RES 0R 1/10W 0402")
      (fields
        (field (name "PACKAGE") "0402")
        (field (name "Comment") "R 0402 1/10W - 0R")
        (field (name "COMPONENTLINK2URL") "D:\\SAVRONIK_SVN\\Donanım\\trunk\\ALTIUM\\Central Library\\Datasheets\\Resistor\\ERJ-2GE0R00X_Datasheet.pdf")
      )
      (libsource (lib "RESISTOR") (part "R 0402 1/10W - 0R"))
    )
    (comp (ref "R127")
      (value "0R")
      (footprint "DISCRETE:RES_0402_N")
      (description "RES 0R 1/10W 0402")
      (fields
        (field (name "PACKAGE") "0402")
        (field (name "Comment") "R 0402 1/10W - 0R")
        (field (name "COMPONENTLINK2URL") "D:\\SAVRONIK_SVN\\Donanım\\trunk\\ALTIUM\\Central Library\\Datasheets\\Resistor\\ERJ-2GE0R00X_Datasheet.pdf")
      )
      (libsource (lib "RESISTOR") (part "R 0402 1/10W - 0R"))
    )
    (comp (ref "R128")
      (value "0R")
      (footprint "DISCRETE:RES_0402_N")
      (description "RES 0R 1/10W 0402")
      (fields
        (field (name "PACKAGE") "0402")
        (field (name "Comment") "R 0402 1/10W - 0R")
        (field (name "COMPONENTLINK2URL") "D:\\SAVRONIK_SVN\\Donanım\\trunk\\ALTIUM\\Central Library\\Datasheets\\Resistor\\ERJ-2GE0R00X_Datasheet.pdf")
      )
      (libsource (lib "RESISTOR") (part "R 0402 1/10W - 0R"))
    )
    (comp (ref "R132")
      (value "0R")
      (footprint "DISCRETE:RES_0402_N")
      (description "RES 0R 1/10W 0402")
      (fields (field (name "PACKAGE") "0402") (field (name "Comment") "R 0402 1/10W - 0R"))
      (libsource (lib "RESISTOR") (part "R 0402 1/10W - 0R"))
    )
    (comp (ref "R133")
      (value "0R")
      (footprint "DISCRETE:RES_0402_N")
      (description "RES 0R 1/10W 0402")
      (fields (field (name "PACKAGE") "0402") (field (name "Comment") "R 0402 1/10W - 0R"))
      (libsource (lib "RESISTOR") (part "R 0402 1/10W - 0R"))
    )
    (comp (ref "U5")
      (value "DBTC-10-4-75+")
      (footprint "AT790-1")
      (description "RF Dir. Coupler 5-1000 MHz SMD 75 OHM -40°C~85°C")
      (libsource (lib "") (part "DBTC-10-4-75+_1"))
    )
    (comp (ref "U6")
      (value "AE427")
      (footprint "SMARTCATV:SOT89")
      (description "IC RF AMP 5-1000MHz GAIN 25dB NF 2dB OIP3 41dBm SOT-89 -40°C~85°C")
      (libsource (lib "SMARTCATV") (part "AE427"))
    )
    (comp (ref "U10")
      (value "PE4312C-Z")
      (footprint "SMARTCATV:QFN_20_PE4312")
      (description "IC RF ATTENUATOR 0.5dB-31.5dB 0.001-4GHz 20-QFN -40°C~85°C")
      (libsource (lib "SMARTCATV") (part "PE4312C-Z"))
    )
    (comp (ref "U12")
      (value "TC1.5-1+")
      (footprint "AT1521")
      (description "RF Balun 0.5-2200 MHz SMD 1:1.5 -20°C~85°C")
      (libsource (lib "SMARTCATV") (part "TC1.5-1+"))
    )
    (comp (ref "U13")
      (value "PE42462A-X")
      (footprint "IC:24_LFCSP(CP-24-8)")
      (description "IC RF SWITCH B 0.01-8GHz 24-QFN -55°C~105°C")
      (libsource (lib "") (part "PE42462A-X_1"))
    )
    (comp (ref "U14")
      (value "PE42462A-X")
      (footprint "IC:24_LFCSP(CP-24-8)")
      (description "IC RF SWITCH B 0.01-8GHz 24-QFN -55°C~105°C")
      (libsource (lib "SMARTCATV") (part "PE42462A-X"))
    )
    (comp (ref "U15")
      (value "TC1.5-1+")
      (footprint "AT1521")
      (description "RF Balun 0.5-2200 MHz SMD 1:1.5 -20°C~85°C")
      (libsource (lib "") (part "TC1.5-1+_1"))
    )
    (comp (ref "U16")
      (value "TC1-1-13M+")
      (footprint "AT1521")
      (description "RF Balun 0.5-2200 MHz SMD 1:1 -40°C~85°C")
      (libsource (lib "SMARTCATV") (part "TC1-1-13M+"))
    )
    (comp (ref "U17")
      (value "AE618")
      (footprint "SOIC-8N_EP")
      (description "IC RF AMP 30-1000MHz GAIN 20dB NF 2.5dB OIP3 44dBm SOIC-8 -40°C~85°C")
      (libsource (lib "SMARTCATV") (part "AE618"))
    )
    (comp (ref "U18")
      (value "TC1-1-13M+")
      (footprint "AT1521")
      (description "RF Balun 0.5-2200 MHz SMD 1:1 -40°C~85°C")
      (libsource (lib "") (part "TC1-1-13M+_1"))
    )
    (comp (ref "U19")
      (value "DBTC-10-4-75+")
      (footprint "AT790-1")
      (description "RF Dir. Coupler 5-1000 MHz SMD 75 OHM -40°C~85°C")
      (libsource (lib "SMARTCATV") (part "DBTC-10-4-75+"))
    )
  )
  (nets
    (net (code "1") (name "+3V3") (class "Default")
      (node (ref "C101") (pin "2") (pinfunction "2_2") (pintype "passive"))
      (node (ref "C105") (pin "2") (pinfunction "2_2") (pintype "passive"))
      (node (ref "C124") (pin "2") (pinfunction "2_2") (pintype "passive"))
      (node (ref "C125") (pin "2") (pinfunction "2_2") (pintype "passive"))
      (node (ref "C126") (pin "2") (pinfunction "2_2") (pintype "passive"))
      (node (ref "C127") (pin "2") (pinfunction "2_2") (pintype "passive"))
      (node (ref "C128") (pin "2") (pinfunction "2_2") (pintype "passive"))
      (node (ref "C129") (pin "2") (pinfunction "2_2") (pintype "passive"))
      (node (ref "C99") (pin "2") (pinfunction "2_2") (pintype "passive"))
      (node (ref "R60") (pin "1") (pinfunction "1_1") (pintype "passive"))
      (node (ref "R62") (pin "1") (pinfunction "1_1") (pintype "passive"))
      (node (ref "U10") (pin "6") (pinfunction "VDD_6") (pintype "passive"))
      (node (ref "U10") (pin "9") (pinfunction "VDD_9") (pintype "passive"))
      (node (ref "U13") (pin "8") (pinfunction "VDD_8") (pintype "passive"))
      (node (ref "U14") (pin "8") (pinfunction "VDD_8") (pintype "passive"))
    )
    (net (code "2") (name "+8V") (class "Default")
      (node (ref "C111") (pin "2") (pinfunction "2_2") (pintype "passive"))
      (node (ref "C136") (pin "2") (pinfunction "2_2") (pintype "passive"))
      (node (ref "C137") (pin "1") (pinfunction "1_1") (pintype "passive"))
      (node (ref "C138") (pin "1") (pinfunction "1_1") (pintype "passive"))
      (node (ref "C153") (pin "1") (pinfunction "1_1") (pintype "passive"))
      (node (ref "C154") (pin "2") (pinfunction "2_2") (pintype "passive"))
      (node (ref "C155") (pin "1") (pinfunction "1_1") (pintype "passive"))
      (node (ref "C60") (pin "2") (pinfunction "2_2") (pintype "passive"))
      (node (ref "C61") (pin "2") (pinfunction "2_2") (pintype "passive"))
      (node (ref "L4") (pin "2") (pinfunction "2_2") (pintype "passive"))
      (node (ref "R88") (pin "2") (pinfunction "2_2") (pintype "passive"))
      (node (ref "R89") (pin "2") (pinfunction "2_2") (pintype "passive"))
      (node (ref "R92") (pin "1") (pinfunction "1_1") (pintype "passive"))
      (node (ref "R93") (pin "1") (pinfunction "1_1") (pintype "passive"))
    )
    (net (code "3") (name "/C0-5_PE4312") (class "Default")
      (node (ref "R128") (pin "2") (pinfunction "2_2") (pintype "passive"))
      (node (ref "U10") (pin "20") (pinfunction "C0.5_20") (pintype "passive"))
    )
    (net (code "4") (name "/C1_PE4312") (class "Default")
      (node (ref "R127") (pin "2") (pinfunction "2_2") (pintype "passive"))
      (node (ref "U10") (pin "19") (pinfunction "C1_19") (pintype "passive"))
    )
    (net (code "5") (name "/C2_PE4312") (class "Default")
      (node (ref "R126") (pin "2") (pinfunction "2_2") (pintype "passive"))
      (node (ref "U10") (pin "17") (pinfunction "C2_17") (pintype "passive"))
    )
    (net (code "6") (name "/C4_PE4312") (class "Default")
      (node (ref "R125") (pin "2") (pinfunction "2_2") (pintype "passive"))
      (node (ref "U10") (pin "16") (pinfunction "C4_16") (pintype "passive"))
    )
    (net (code "7") (name "/C8_PE4312") (class "Default")
      (node (ref "R59") (pin "2") (pinfunction "2_2") (pintype "passive"))
      (node (ref "U10") (pin "15") (pinfunction "C8_15") (pintype "passive"))
    )
    (net (code "8") (name "/C16_PE4312") (class "Default")
      (node (ref "R58") (pin "2") (pinfunction "2_2") (pintype "passive"))
      (node (ref "U10") (pin "1") (pinfunction "C16_1") (pintype "passive"))
    )
    (net (code "9") (name "/COUPLED_1") (class "Default")
      (node (ref "U5") (pin "1") (pinfunction "COUPLED_1") (pintype "passive"))
    )
    (net (code "10") (name "/COUPLED_2") (class "Default")
      (node (ref "U19") (pin "1") (pinfunction "COUPLED_1") (pintype "passive"))
    )
    (net (code "11") (name "/EQ_RF_IN_2") (class "Default")
      (node (ref "U13") (pin "2") (pinfunction "RF2_2") (pintype "passive"))
    )
    (net (code "12") (name "/EQ_RF_IN_3") (class "Default")
      (node (ref "U13") (pin "4") (pinfunction "RF3_4") (pintype "passive"))
    )
    (net (code "13") (name "/EQ_RF_IN_4") (class "Default")
      (node (ref "U13") (pin "15") (pinfunction "RF4_15") (pintype "passive"))
    )
    (net (code "14") (name "/EQ_RF_IN_5") (class "Default")
      (node (ref "U13") (pin "17") (pinfunction "RF5_17") (pintype "passive"))
    )
    (net (code "15") (name "/EQ_RF_IN_6") (class "Default")
      (node (ref "U13") (pin "19") (pinfunction "RF6_19") (pintype "passive"))
    )
    (net (code "16") (name "/EQ_RF_OUT_2") (class "Default")
      (node (ref "U14") (pin "17") (pinfunction "RF5_17") (pintype "passive"))
    )
    (net (code "17") (name "/EQ_RF_OUT_3") (class "Default")
      (node (ref "U14") (pin "15") (pinfunction "RF4_15") (pintype "passive"))
    )
    (net (code "18") (name "/EQ_RF_OUT_4") (class "Default")
      (node (ref "U14") (pin "4") (pinfunction "RF3_4") (pintype "passive"))
    )
    (net (code "19") (name "/EQ_RF_OUT_5") (class "Default")
      (node (ref "U14") (pin "2") (pinfunction "RF2_2") (pintype "passive"))
    )
    (net (code "20") (name "/EQ_RF_OUT_6") (class "Default")
      (node (ref "U14") (pin "24") (pinfunction "RF1_24") (pintype "passive"))
    )
    (net (code "21") (name "/L1_1_PE42462") (class "Default")
      (node (ref "R64") (pin "2") (pinfunction "2_2") (pintype "passive"))
      (node (ref "R78") (pin "1") (pinfunction "1_1") (pintype "passive"))
    )
    (net (code "22") (name "/L1_2_PE42462") (class "Default")
      (node (ref "R71") (pin "2") (pinfunction "2_2") (pintype "passive"))
      (node (ref "R79") (pin "2") (pinfunction "2_2") (pintype "passive"))
    )
    (net (code "23") (name "/L2_1_PE42462") (class "Default")
      (node (ref "R65") (pin "2") (pinfunction "2_2") (pintype "passive"))
      (node (ref "R76") (pin "1") (pinfunction "1_1") (pintype "passive"))
    )
    (net (code "24") (name "/L2_2_PE42462") (class "Default")
      (node (ref "R70") (pin "2") (pinfunction "2_2") (pintype "passive"))
      (node (ref "R77") (pin "2") (pinfunction "2_2") (pintype "passive"))
    )
    (net (code "25") (name "/L3_1_PE42462") (class "Default")
      (node (ref "R66") (pin "2") (pinfunction "2_2") (pintype "passive"))
      (node (ref "R74") (pin "1") (pinfunction "1_1") (pintype "passive"))
    )
    (net (code "26") (name "/L3_2_PE42462") (class "Default")
      (node (ref "R69") (pin "2") (pinfunction "2_2") (pintype "passive"))
      (node (ref "R75") (pin "2") (pinfunction "2_2") (pintype "passive"))
    )
    (net (code "27") (name "/LE_PE4312") (class "Default")
      (node (ref "R53") (pin "1") (pinfunction "1_1") (pintype "passive"))
    )
    (net (code "28") (name "/bypass_lane") (class "Default")
      (node (ref "C106") (pin "2") (pinfunction "2_2") (pintype "passive"))
      (node (ref "C149") (pin "2") (pinfunction "2_2") (pintype "passive"))
    )
    (net (code "29") (name "GND") (class "Default")
      (node (ref "C101") (pin "1") (pinfunction "1_1") (pintype "passive"))
      (node (ref "C105") (pin "1") (pinfunction "1_1") (pintype "passive"))
      (node (ref "C111") (pin "1") (pinfunction "1_1") (pintype "passive"))
      (node (ref "C118") (pin "1") (pinfunction "1_1") (pintype "passive"))
      (node (ref "C119") (pin "1") (pinfunction "1_1") (pintype "passive"))
      (node (ref "C120") (pin "1") (pinfunction "1_1") (pintype "passive"))
      (node (ref "C121") (pin "1") (pinfunction "1_1") (pintype "passive"))
      (node (ref "C122") (pin "1") (pinfunction "1_1") (pintype "passive"))
      (node (ref "C123") (pin "1") (pinfunction "1_1") (pintype "passive"))
      (node (ref "C124") (pin "1") (pinfunction "1_1") (pintype "passive"))
      (node (ref "C125") (pin "1") (pinfunction "1_1") (pintype "passive"))
      (node (ref "C126") (pin "1") (pinfunction "1_1") (pintype "passive"))
      (node (ref "C127") (pin "1") (pinfunction "1_1") (pintype "passive"))
      (node (ref "C128") (pin "1") (pinfunction "1_1") (pintype "passive"))
      (node (ref "C129") (pin "1") (pinfunction "1_1") (pintype "passive"))
      (node (ref "C136") (pin "1") (pinfunction "1_1") (pintype "passive"))
      (node (ref "C137") (pin "2") (pinfunction "2_2") (pintype "passive"))
      (node (ref "C138") (pin "2") (pinfunction "2_2") (pintype "passive"))
      (node (ref "C153") (pin "2") (pinfunction "2_2") (pintype "passive"))
      (node (ref "C154") (pin "1") (pinfunction "1_1") (pintype "passive"))
      (node (ref "C155") (pin "2") (pinfunction "2_2") (pintype "passive"))
      (node (ref "C159") (pin "1") (pinfunction "1_1") (pintype "passive"))
      (node (ref "C168") (pin "1") (pinfunction "1_1") (pintype "passive"))
      (node (ref "C60") (pin "1") (pinfunction "1_1") (pintype "passive"))
      (node (ref "C61") (pin "1") (pinfunction "1_1") (pintype "passive"))
      (node (ref "C99") (pin "1") (pinfunction "1_1") (pintype "passive"))
      (node (ref "DPX1") (pin "1") (pinfunction "GND_1") (pintype "passive"))
      (node (ref "DPX1") (pin "10") (pinfunction "GND_10") (pintype "passive"))
      (node (ref "DPX1") (pin "11") (pinfunction "GND_11") (pintype "passive"))
      (node (ref "DPX1") (pin "12") (pinfunction "GND_12") (pintype "passive"))
      (node (ref "DPX1") (pin "13") (pinfunction "GND_13") (pintype "passive"))
      (node (ref "DPX1") (pin "14") (pinfunction "GND_14") (pintype "passive"))
      (node (ref "DPX1") (pin "15") (pinfunction "GND_15") (pintype "passive"))
      (node (ref "DPX1") (pin "16") (pinfunction "GND_16") (pintype "passive"))
      (node (ref "DPX1") (pin "17") (pinfunction "GND_17") (pintype "passive"))
      (node (ref "DPX1") (pin "19") (pinfunction "GND_19") (pintype "passive"))
      (node (ref "DPX1") (pin "2") (pinfunction "GND_2") (pintype "passive"))
      (node (ref "DPX1") (pin "3") (pinfunction "GND_3") (pintype "passive"))
      (node (ref "DPX1") (pin "4") (pinfunction "GND_4") (pintype "passive"))
      (node (ref "DPX1") (pin "5") (pinfunction "GND_5") (pintype "passive"))
      (node (ref "DPX1") (pin "6") (pinfunction "GND_6") (pintype "passive"))
      (node (ref "DPX1") (pin "8") (pinfunction "GND_8") (pintype "passive"))
      (node (ref "DPX2") (pin "1") (pinfunction "GND_1") (pintype "passive"))
      (node (ref "DPX2") (pin "10") (pinfunction "GND_10") (pintype "passive"))
      (node (ref "DPX2") (pin "11") (pinfunction "GND_11") (pintype "passive"))
      (node (ref "DPX2") (pin "12") (pinfunction "GND_12") (pintype "passive"))
      (node (ref "DPX2") (pin "13") (pinfunction "GND_13") (pintype "passive"))
      (node (ref "DPX2") (pin "14") (pinfunction "GND_14") (pintype "passive"))
      (node (ref "DPX2") (pin "15") (pinfunction "GND_15") (pintype "passive"))
      (node (ref "DPX2") (pin "16") (pinfunction "GND_16") (pintype "passive"))
      (node (ref "DPX2") (pin "17") (pinfunction "GND_17") (pintype "passive"))
      (node (ref "DPX2") (pin "19") (pinfunction "GND_19") (pintype "passive"))
      (node (ref "DPX2") (pin "2") (pinfunction "GND_2") (pintype "passive"))
      (node (ref "DPX2") (pin "3") (pinfunction "GND_3") (pintype "passive"))
      (node (ref "DPX2") (pin "4") (pinfunction "GND_4") (pintype "passive"))
      (node (ref "DPX2") (pin "5") (pinfunction "GND_5") (pintype "passive"))
      (node (ref "DPX2") (pin "6") (pinfunction "GND_6") (pintype "passive"))
      (node (ref "DPX2") (pin "8") (pinfunction "GND_8") (pintype "passive"))
      (node (ref "J10") (pin "G1") (pinfunction "G1_G1") (pintype "power_in"))
      (node (ref "J10") (pin "G2") (pinfunction "G2_G2") (pintype "power_in"))
      (node (ref "J11") (pin "G1") (pinfunction "G1_G1") (pintype "power_in"))
      (node (ref "J11") (pin "G2") (pinfunction "G2_G2") (pintype "power_in"))
      (node (ref "J12") (pin "G1") (pinfunction "G1_G1") (pintype "power_in"))
      (node (ref "J12") (pin "G2") (pinfunction "G2_G2") (pintype "power_in"))
      (node (ref "J6") (pin "2") (pinfunction "GND_2") (pintype "passive"))
      (node (ref "J7") (pin "2") (pinfunction "GND_2") (pintype "passive"))
      (node (ref "J9") (pin "G1") (pinfunction "G1_G1") (pintype "power_in"))
      (node (ref "J9") (pin "G2") (pinfunction "G2_G2") (pintype "power_in"))
      (node (ref "R50") (pin "1") (pinfunction "1_1") (pintype "passive"))
      (node (ref "R51") (pin "1") (pinfunction "1_1") (pintype "passive"))
      (node (ref "R52") (pin "1") (pinfunction "1_1") (pintype "passive"))
      (node (ref "R54") (pin "1") (pinfunction "1_1") (pintype "passive"))
      (node (ref "R56") (pin "2") (pinfunction "2_2") (pintype "passive"))
      (node (ref "R61") (pin "1") (pinfunction "1_1") (pintype "passive"))
      (node (ref "R63") (pin "1") (pinfunction "1_1") (pintype "passive"))
      (node (ref "R64") (pin "1") (pinfunction "1_1") (pintype "passive"))
      (node (ref "R65") (pin "1") (pinfunction "1_1") (pintype "passive"))
      (node (ref "R66") (pin "1") (pinfunction "1_1") (pintype "passive"))
      (node (ref "R69") (pin "1") (pinfunction "1_1") (pintype "passive"))
      (node (ref "R70") (pin "1") (pinfunction "1_1") (pintype "passive"))
      (node (ref "R71") (pin "1") (pinfunction "1_1") (pintype "passive"))
      (node (ref "R72") (pin "1") (pinfunction "1_1") (pintype "passive"))
      (node (ref "R82") (pin "1") (pinfunction "1_1") (pintype "passive"))
      (node (ref "R83") (pin "1") (pinfunction "1_1") (pintype "passive"))
      (node (ref "R84") (pin "1") (pinfunction "1_1") (pintype "passive"))
      (node (ref "R85") (pin "1") (pinfunction "1_1") (pintype "passive"))
      (node (ref "R90") (pin "2") (pinfunction "2_2") (pintype "passive"))
      (node (ref "R91") (pin "1") (pinfunction "1_1") (pintype "passive"))
      (node (ref "U10") (pin "10") (pinfunction "GND_10") (pintype "passive"))
      (node (ref "U10") (pin "11") (pinfunction "GND_11") (pintype "passive"))
      (node (ref "U10") (pin "12") (pinfunction "GND/VSS_12") (pintype "passive"))
      (node (ref "U10") (pin "18") (pinfunction "GND_18") (pintype "passive"))
      (node (ref "U10") (pin "21") (pinfunction "GND_21") (pintype "passive"))
      (node (ref "U12") (pin "4") (pinfunction "GND_4") (pintype "passive"))
      (node (ref "U13") (pin "12") (pinfunction "GND_12") (pintype "passive"))
      (node (ref "U13") (pin "13") (pinfunction "GND_13") (pintype "passive"))
      (node (ref "U13") (pin "14") (pinfunction "GND_14") (pintype "passive"))
      (node (ref "U13") (pin "16") (pinfunction "GND_16") (pintype "passive"))
      (node (ref "U13") (pin "18") (pinfunction "GND_18") (pintype "passive"))
      (node (ref "U13") (pin "20") (pinfunction "NC_20") (pintype "passive"))
      (node (ref "U13") (pin "21") (pinfunction "GND_21") (pintype "passive"))
      (node (ref "U13") (pin "23") (pinfunction "GND_23") (pintype "passive"))
      (node (ref "U13") (pin "25") (pinfunction "GND_25") (pintype "passive"))
      (node (ref "U13") (pin "3") (pinfunction "GND_3") (pintype "passive"))
      (node (ref "U13") (pin "5") (pinfunction "GND_5") (pintype "passive"))
      (node (ref "U13") (pin "6") (pinfunction "GND_6") (pintype "passive"))
      (node (ref "U13") (pin "7") (pinfunction "GND_7") (pintype "passive"))
      (node (ref "U14") (pin "12") (pinfunction "GND_12") (pintype "passive"))
      (node (ref "U14") (pin "13") (pinfunction "GND_13") (pintype "passive"))
      (node (ref "U14") (pin "14") (pinfunction "GND_14") (pintype "passive"))
      (node (ref "U14") (pin "16") (pinfunction "GND_16") (pintype "passive"))
      (node (ref "U14") (pin "18") (pinfunction "GND_18") (pintype "passive"))
      (node (ref "U14") (pin "20") (pinfunction "NC_20") (pintype "passive"))
      (node (ref "U14") (pin "21") (pinfunction "GND_21") (pintype "passive"))
      (node (ref "U14") (pin "23") (pinfunction "GND_23") (pintype "passive"))
      (node (ref "U14") (pin "25") (pinfunction "GND_25") (pintype "passive"))
      (node (ref "U14") (pin "3") (pinfunction "GND_3") (pintype "passive"))
      (node (ref "U14") (pin "5") (pinfunction "GND_5") (pintype "passive"))
      (node (ref "U14") (pin "6") (pinfunction "GND_6") (pintype "passive"))
      (node (ref "U14") (pin "7") (pinfunction "GND_7") (pintype "passive"))
      (node (ref "U15") (pin "4") (pinfunction "GND_4") (pintype "passive"))
      (node (ref "U16") (pin "4") (pinfunction "P_4") (pintype "passive"))
      (node (ref "U17") (pin "2") (pinfunction "GND_2") (pintype "passive"))
      (node (ref "U17") (pin "3") (pinfunction "GND_3") (pintype "passive"))
      (node (ref "U17") (pin "6") (pinfunction "GND_6") (pintype "passive"))
      (node (ref "U17") (pin "7") (pinfunction "GND_7") (pintype "passive"))
      (node (ref "U17") (pin "9") (pinfunction "GND_9") (pintype "passive"))
      (node (ref "U18") (pin "6") (pinfunction "PD_6") (pintype "passive"))
      (node (ref "U19") (pin "2") (pinfunction "GND_2") (pintype "passive"))
      (node (ref "U5") (pin "2") (pinfunction "GND_2") (pintype "passive"))
      (node (ref "U6") (pin "2") (pinfunction "GND_2") (pintype "passive"))
    )
    (net (code "30") (name "Net-(C110-Pad2)") (class "Default")
      (node (ref "C110") (pin "2") (pinfunction "2_2") (pintype "passive"))
      (node (ref "J9") (pin "A") (pinfunction "A_A") (pintype "passive"))
    )
    (net (code "31") (name "Net-(C112-Pad1)") (class "Default")
      (node (ref "C112") (pin "1") (pinfunction "1_1") (pintype "passive"))
      (node (ref "R49") (pin "2") (pinfunction "2_2") (pintype "passive"))
      (node (ref "R51") (pin "2") (pinfunction "2_2") (pintype "passive"))
    )
    (net (code "32") (name "Net-(C113-Pad2)") (class "Default")
      (node (ref "C113") (pin "2") (pinfunction "2_2") (pintype "passive"))
      (node (ref "J10") (pin "C") (pinfunction "C_C") (pintype "passive"))
    )
    (net (code "33") (name "Net-(C117-Pad1)") (class "Default")
      (node (ref "C117") (pin "1") (pinfunction "1_1") (pintype "passive"))
      (node (ref "L19") (pin "2") (pinfunction "2_2") (pintype "passive"))
    )
    (net (code "34") (name "Net-(C118-Pad2)") (class "Default")
      (node (ref "C118") (pin "2") (pinfunction "2_2") (pintype "passive"))
      (node (ref "R58") (pin "1") (pinfunction "1_1") (pintype "passive"))
    )
    (net (code "35") (name "Net-(C119-Pad2)") (class "Default")
      (node (ref "C119") (pin "2") (pinfunction "2_2") (pintype "passive"))
      (node (ref "R59") (pin "1") (pinfunction "1_1") (pintype "passive"))
    )
    (net (code "36") (name "Net-(C120-Pad2)") (class "Default")
      (node (ref "C120") (pin "2") (pinfunction "2_2") (pintype "passive"))
      (node (ref "R125") (pin "1") (pinfunction "1_1") (pintype "passive"))
    )
    (net (code "37") (name "Net-(C121-Pad2)") (class "Default")
      (node (ref "C121") (pin "2") (pinfunction "2_2") (pintype "passive"))
      (node (ref "R126") (pin "1") (pinfunction "1_1") (pintype "passive"))
    )
    (net (code "38") (name "Net-(C122-Pad2)") (class "Default")
      (node (ref "C122") (pin "2") (pinfunction "2_2") (pintype "passive"))
      (node (ref "R127") (pin "1") (pinfunction "1_1") (pintype "passive"))
    )
    (net (code "39") (name "Net-(C123-Pad2)") (class "Default")
      (node (ref "C123") (pin "2") (pinfunction "2_2") (pintype "passive"))
      (node (ref "R128") (pin "1") (pinfunction "1_1") (pintype "passive"))
    )
    (net (code "40") (name "Net-(C130-Pad2)") (class "Default")
      (node (ref "C130") (pin "2") (pinfunction "2_2") (pintype "passive"))
      (node (ref "C131") (pin "2") (pinfunction "2_2") (pintype "passive"))
    )
    (net (code "41") (name "Net-(C132-Pad1)") (class "Default")
      (node (ref "C132") (pin "1") (pinfunction "1_1") (pintype "passive"))
      (node (ref "R80") (pin "2") (pinfunction "2_2") (pintype "passive"))
      (node (ref "R83") (pin "2") (pinfunction "2_2") (pintype "passive"))
    )
    (net (code "42") (name "Net-(C133-Pad2)") (class "Default")
      (node (ref "C133") (pin "2") (pinfunction "2_2") (pintype "passive"))
      (node (ref "R81") (pin "1") (pinfunction "1_1") (pintype "passive"))
      (node (ref "R84") (pin "2") (pinfunction "2_2") (pintype "passive"))
    )
    (net (code "43") (name "Net-(C134-Pad1)") (class "Default")
      (node (ref "C134") (pin "1") (pinfunction "1_1") (pintype "passive"))
      (node (ref "J11") (pin "A") (pinfunction "A_A") (pintype "passive"))
    )
    (net (code "44") (name "Net-(C135-Pad2)") (class "Default")
      (node (ref "C135") (pin "2") (pinfunction "2_2") (pintype "passive"))
      (node (ref "R108") (pin "1") (pinfunction "1_1") (pintype "passive"))
      (node (ref "R132") (pin "1") (pinfunction "1_1") (pintype "passive"))
    )
    (net (code "45") (name "Net-(C139-Pad1)") (class "Default")
      (node (ref "C139") (pin "1") (pinfunction "1_1") (pintype "passive"))
      (node (ref "R86") (pin "2") (pinfunction "2_2") (pintype "passive"))
    )
    (net (code "46") (name "Net-(C139-Pad2)") (class "Default")
      (node (ref "C139") (pin "2") (pinfunction "2_2") (pintype "passive"))
      (node (ref "R87") (pin "1") (pinfunction "1_1") (pintype "passive"))
    )
    (net (code "47") (name "Net-(C140-Pad1)") (class "Default")
      (node (ref "C140") (pin "1") (pinfunction "1_1") (pintype "passive"))
      (node (ref "R87") (pin "2") (pinfunction "2_2") (pintype "passive"))
    )
    (net (code "48") (name "Net-(C142-Pad1)") (class "Default")
      (node (ref "C142") (pin "1") (pinfunction "1_1") (pintype "passive"))
      (node (ref "J12") (pin "A") (pinfunction "A_A") (pintype "passive"))
    )
    (net (code "49") (name "Net-(C143-Pad2)") (class "Default")
      (node (ref "C143") (pin "2") (pinfunction "2_2") (pintype "passive"))
      (node (ref "J12") (pin "C") (pinfunction "C_C") (pintype "passive"))
    )
    (net (code "50") (name "Net-(C144-Pad1)") (class "Default")
      (node (ref "C144") (pin "1") (pinfunction "1_1") (pintype "passive"))
      (node (ref "R109") (pin "2") (pinfunction "2_2") (pintype "passive"))
      (node (ref "R133") (pin "1") (pinfunction "1_1") (pintype "passive"))
    )
    (net (code "51") (name "Net-(C151-Pad1)") (class "Default")
      (node (ref "C151") (pin "1") (pinfunction "1_1") (pintype "passive"))
      (node (ref "R94") (pin "2") (pinfunction "2_2") (pintype "passive"))
    )
    (net (code "52") (name "Net-(C151-Pad2)") (class "Default")
      (node (ref "C151") (pin "2") (pinfunction "2_2") (pintype "passive"))
      (node (ref "R95") (pin "1") (pinfunction "1_1") (pintype "passive"))
    )
    (net (code "53") (name "Net-(C152-Pad1)") (class "Default")
      (node (ref "C152") (pin "1") (pinfunction "1_1") (pintype "passive"))
      (node (ref "R95") (pin "2") (pinfunction "2_2") (pintype "passive"))
    )
    (net (code "54") (name "Net-(C158-Pad1)") (class "Default")
      (node (ref "C158") (pin "1") (pinfunction "1_1") (pintype "passive"))
      (node (ref "L13") (pin "1") (pinfunction "1_1") (pintype "passive"))
      (node (ref "R107") (pin "1") (pinfunction "1_1") (pintype "passive"))
      (node (ref "R132") (pin "2") (pinfunction "2_2") (pintype "passive"))
    )
    (net (code "55") (name "Net-(C158-Pad2)") (class "Default")
      (node (ref "C158") (pin "2") (pinfunction "2_2") (pintype "passive"))
      (node (ref "R106") (pin "1") (pinfunction "1_1") (pintype "passive"))
    )
    (net (code "56") (name "Net-(C159-Pad2)") (class "Default")
      (node (ref "C159") (pin "2") (pinfunction "2_2") (pintype "passive"))
      (node (ref "L18") (pin "1") (pinfunction "1_1") (pintype "passive"))
    )
    (net (code "57") (name "Net-(C169-Pad1)") (class "Default")
      (node (ref "C169") (pin "1") (pinfunction "1_1") (pintype "passive"))
      (node (ref "R5") (pin "1") (pinfunction "1_1") (pintype "passive"))
    )
    (net (code "58") (name "Net-(C169-Pad2)") (class "Default")
      (node (ref "C169") (pin "2") (pinfunction "2_2") (pintype "passive"))
      (node (ref "R6") (pin "1") (pinfunction "1_1") (pintype "passive"))
    )
    (net (code "59") (name "Net-(DPX1-CP)") (class "Default")
      (node (ref "C108") (pin "2") (pinfunction "2_2") (pintype "passive"))
      (node (ref "DPX1") (pin "18") (pinfunction "CP_18") (pintype "passive"))
    )
    (net (code "60") (name "Net-(DPX1-HPP)") (class "Default")
      (node (ref "C109") (pin "1") (pinfunction "1_1") (pintype "passive"))
      (node (ref "DPX1") (pin "7") (pinfunction "HPP_7") (pintype "passive"))
    )
    (net (code "61") (name "Net-(DPX1-LPP)") (class "Default")
      (node (ref "C106") (pin "1") (pinfunction "1_1") (pintype "passive"))
      (node (ref "DPX1") (pin "9") (pinfunction "LPP_9") (pintype "passive"))
    )
    (net (code "62") (name "Net-(DPX2-CP)") (class "Default")
      (node (ref "C146") (pin "2") (pinfunction "2_2") (pintype "passive"))
      (node (ref "DPX2") (pin "18") (pinfunction "CP_18") (pintype "passive"))
    )
    (net (code "63") (name "Net-(DPX2-HPP)") (class "Default")
      (node (ref "C143") (pin "1") (pinfunction "1_1") (pintype "passive"))
      (node (ref "DPX2") (pin "7") (pinfunction "HPP_7") (pintype "passive"))
    )
    (net (code "64") (name "Net-(DPX2-LPP)") (class "Default")
      (node (ref "C149") (pin "1") (pinfunction "1_1") (pintype "passive"))
      (node (ref "DPX2") (pin "9") (pinfunction "LPP_9") (pintype "passive"))
    )
    (net (code "65") (name "Net-(J6-RF)") (class "Default")
      (node (ref "C107") (pin "1") (pinfunction "1_1") (pintype "passive"))
      (node (ref "J6") (pin "1") (pinfunction "RF_1") (pintype "passive"))
    )
    (net (code "66") (name "Net-(J7-RF)") (class "Default")
      (node (ref "C147") (pin "1") (pinfunction "1_1") (pintype "passive"))
      (node (ref "J7") (pin "1") (pinfunction "RF_1") (pintype "passive"))
    )
    (net (code "67") (name "Net-(J9-PadC)") (class "Default")
      (node (ref "J9") (pin "C") (pinfunction "C_C") (pintype "passive"))
      (node (ref "R49") (pin "1") (pinfunction "1_1") (pintype "passive"))
      (node (ref "R50") (pin "2") (pinfunction "2_2") (pintype "passive"))
    )
    (net (code "68") (name "Net-(J10-PadA)") (class "Default")
      (node (ref "J10") (pin "A") (pinfunction "A_A") (pintype "passive"))
      (node (ref "R80") (pin "1") (pinfunction "1_1") (pintype "passive"))
      (node (ref "R82") (pin "2") (pinfunction "2_2") (pintype "passive"))
    )
    (net (code "69") (name "Net-(J11-PadC)") (class "Default")
      (node (ref "J11") (pin "C") (pinfunction "C_C") (pintype "passive"))
      (node (ref "R81") (pin "2") (pinfunction "2_2") (pintype "passive"))
      (node (ref "R85") (pin "2") (pinfunction "2_2") (pintype "passive"))
    )
    (net (code "70") (name "Net-(L5-Pad2)") (class "Default")
      (node (ref "L5") (pin "2") (pinfunction "2_2") (pintype "passive"))
      (node (ref "R88") (pin "1") (pinfunction "1_1") (pintype "passive"))
      (node (ref "R89") (pin "1") (pinfunction "1_1") (pintype "passive"))
    )
    (net (code "71") (name "Net-(L6-Pad1)") (class "Default")
      (node (ref "L6") (pin "1") (pinfunction "1_1") (pintype "passive"))
      (node (ref "R92") (pin "2") (pinfunction "2_2") (pintype "passive"))
      (node (ref "R93") (pin "2") (pinfunction "2_2") (pintype "passive"))
    )
    (net (code "72") (name "Net-(L13-Pad2)") (class "Default")
      (node (ref "L13") (pin "2") (pinfunction "2_2") (pintype "passive"))
      (node (ref "R106") (pin "2") (pinfunction "2_2") (pintype "passive"))
      (node (ref "R107") (pin "2") (pinfunction "2_2") (pintype "passive"))
      (node (ref "R133") (pin "2") (pinfunction "2_2") (pintype "passive"))
    )
    (net (code "73") (name "Net-(L18-Pad2)") (class "Default")
      (node (ref "L18") (pin "2") (pinfunction "2_2") (pintype "passive"))
      (node (ref "R114") (pin "1") (pinfunction "1_1") (pintype "passive"))
    )
    (net (code "74") (name "Net-(R108-Pad2)") (class "Default")
      (node (ref "R108") (pin "2") (pinfunction "2_2") (pintype "passive"))
      (node (ref "R109") (pin "1") (pinfunction "1_1") (pintype "passive"))
      (node (ref "R114") (pin "2") (pinfunction "2_2") (pintype "passive"))
    )
    (net (code "75") (name "Net-(U5-RF_IN)") (class "Default")
      (node (ref "C107") (pin "2") (pinfunction "2_2") (pintype "passive"))
      (node (ref "U5") (pin "3") (pinfunction "RF_IN_3") (pintype "passive"))
    )
    (net (code "76") (name "Net-(U5-RF_OUT)") (class "Default")
      (node (ref "C108") (pin "1") (pinfunction "1_1") (pintype "passive"))
      (node (ref "U5") (pin "4") (pinfunction "RF_OUT_4") (pintype "passive"))
    )
    (net (code "77") (name "Net-(U6-RF_IN)") (class "Default")
      (node (ref "C112") (pin "2") (pinfunction "2_2") (pintype "passive"))
      (node (ref "R5") (pin "2") (pinfunction "2_2") (pintype "passive"))
      (node (ref "U6") (pin "1") (pinfunction "RF_IN_1") (pintype "passive"))
    )
    (net (code "78") (name "Net-(U6-RF_OUT)") (class "Default")
      (node (ref "C168") (pin "2") (pinfunction "2_2") (pintype "passive"))
      (node (ref "L19") (pin "1") (pinfunction "1_1") (pintype "passive"))
      (node (ref "L4") (pin "1") (pinfunction "1_1") (pintype "passive"))
      (node (ref "R6") (pin "2") (pinfunction "2_2") (pintype "passive"))
      (node (ref "U6") (pin "3") (pinfunction "RF_OUT_3") (pintype "passive"))
    )
    (net (code "79") (name "Net-(U10-Clock)") (class "Default")
      (node (ref "R54") (pin "2") (pinfunction "2_2") (pintype "passive"))
      (node (ref "U10") (pin "4") (pinfunction "Clock_4") (pintype "passive"))
    )
    (net (code "80") (name "Net-(U10-Data)") (class "Default")
      (node (ref "R56") (pin "1") (pinfunction "1_1") (pintype "passive"))
      (node (ref "U10") (pin "3") (pinfunction "Data_3") (pintype "passive"))
    )
    (net (code "81") (name "Net-(U10-LE)") (class "Default")
      (node (ref "R53") (pin "2") (pinfunction "2_2") (pintype "passive"))
      (node (ref "U10") (pin "5") (pinfunction "LE_5") (pintype "passive"))
    )
    (net (code "82") (name "Net-(U10-PUP1)") (class "Default")
      (node (ref "R60") (pin "2") (pinfunction "2_2") (pintype "passive"))
      (node (ref "R61") (pin "2") (pinfunction "2_2") (pintype "passive"))
      (node (ref "U10") (pin "7") (pinfunction "PUP1_7") (pintype "passive"))
    )
    (net (code "83") (name "Net-(U10-PUP2)") (class "Default")
      (node (ref "R62") (pin "2") (pinfunction "2_2") (pintype "passive"))
      (node (ref "R63") (pin "2") (pinfunction "2_2") (pintype "passive"))
      (node (ref "U10") (pin "8") (pinfunction "PUP2_8") (pintype "passive"))
    )
    (net (code "84") (name "Net-(U10-P{slash}S)") (class "Default")
      (node (ref "R52") (pin "2") (pinfunction "2_2") (pintype "passive"))
      (node (ref "U10") (pin "13") (pinfunction "P/S_13") (pintype "passive"))
    )
    (net (code "85") (name "Net-(U10-RF1)") (class "Default")
      (node (ref "C117") (pin "2") (pinfunction "2_2") (pintype "passive"))
      (node (ref "U10") (pin "2") (pinfunction "RF1_2") (pintype "passive"))
    )
    (net (code "86") (name "Net-(U10-RF2)") (class "Default")
      (node (ref "C113") (pin "1") (pinfunction "1_1") (pintype "passive"))
      (node (ref "U10") (pin "14") (pinfunction "RF2_14") (pintype "passive"))
    )
    (net (code "87") (name "Net-(U12-PD)") (class "Default")
      (node (ref "C110") (pin "1") (pinfunction "1_1") (pintype "passive"))
      (node (ref "U12") (pin "6") (pinfunction "PD_6") (pintype "passive"))
    )
    (net (code "88") (name "Net-(U12-SD)") (class "Default")
      (node (ref "C109") (pin "2") (pinfunction "2_2") (pintype "passive"))
      (node (ref "U12") (pin "1") (pinfunction "SD_1") (pintype "passive"))
    )
    (net (code "89") (name "Net-(U13-LS)") (class "Default")
      (node (ref "R72") (pin "2") (pinfunction "2_2") (pintype "passive"))
      (node (ref "U13") (pin "1") (pinfunction "LS_1") (pintype "passive"))
    )
    (net (code "90") (name "Net-(U13-RF1)") (class "Default")
      (node (ref "C130") (pin "1") (pinfunction "1_1") (pintype "passive"))
      (node (ref "U13") (pin "24") (pinfunction "RF1_24") (pintype "passive"))
    )
    (net (code "91") (name "Net-(U13-RFC)") (class "Default")
      (node (ref "C132") (pin "2") (pinfunction "2_2") (pintype "passive"))
      (node (ref "U13") (pin "22") (pinfunction "RFC_22") (pintype "passive"))
    )
    (net (code "92") (name "Net-(U13-V1)") (class "Default")
      (node (ref "R78") (pin "2") (pinfunction "2_2") (pintype "passive"))
      (node (ref "U13") (pin "9") (pinfunction "V1_9") (pintype "passive"))
    )
    (net (code "93") (name "Net-(U13-V2)") (class "Default")
      (node (ref "R76") (pin "2") (pinfunction "2_2") (pintype "passive"))
      (node (ref "U13") (pin "10") (pinfunction "V2_10") (pintype "passive"))
    )
    (net (code "94") (name "Net-(U13-V3)") (class "Default")
      (node (ref "R74") (pin "2") (pinfunction "2_2") (pintype "passive"))
      (node (ref "U13") (pin "11") (pinfunction "V3_11") (pintype "passive"))
    )
    (net (code "95") (name "Net-(U14-RF6)") (class "Default")
      (node (ref "C131") (pin "1") (pinfunction "1_1") (pintype "passive"))
      (node (ref "U14") (pin "19") (pinfunction "RF6_19") (pintype "passive"))
    )
    (net (code "96") (name "Net-(U14-RFC)") (class "Default")
      (node (ref "C133") (pin "1") (pinfunction "1_1") (pintype "passive"))
      (node (ref "U14") (pin "22") (pinfunction "RFC_22") (pintype "passive"))
    )
    (net (code "97") (name "Net-(U14-V1)") (class "Default")
      (node (ref "R79") (pin "1") (pinfunction "1_1") (pintype "passive"))
      (node (ref "U14") (pin "9") (pinfunction "V1_9") (pintype "passive"))
    )
    (net (code "98") (name "Net-(U14-V2)") (class "Default")
      (node (ref "R77") (pin "1") (pinfunction "1_1") (pintype "passive"))
      (node (ref "U14") (pin "10") (pinfunction "V2_10") (pintype "passive"))
    )
    (net (code "99") (name "Net-(U14-V3)") (class "Default")
      (node (ref "R75") (pin "1") (pinfunction "1_1") (pintype "passive"))
      (node (ref "U14") (pin "11") (pinfunction "V3_11") (pintype "passive"))
    )
    (net (code "100") (name "Net-(U15-PD)") (class "Default")
      (node (ref "C134") (pin "2") (pinfunction "2_2") (pintype "passive"))
      (node (ref "U15") (pin "6") (pinfunction "PD_6") (pintype "passive"))
    )
    (net (code "101") (name "Net-(U15-SD)") (class "Default")
      (node (ref "C135") (pin "1") (pinfunction "1_1") (pintype "passive"))
      (node (ref "U15") (pin "1") (pinfunction "SD_1") (pintype "passive"))
    )
    (net (code "102") (name "Net-(U16-PD)") (class "Default")
      (node (ref "C144") (pin "2") (pinfunction "2_2") (pintype "passive"))
      (node (ref "U16") (pin "6") (pinfunction "PD_6") (pintype "passive"))
    )
    (net (code "103") (name "Net-(U16-S)") (class "Default")
      (node (ref "C150") (pin "1") (pinfunction "1_1") (pintype "passive"))
      (node (ref "U16") (pin "3") (pinfunction "S_3") (pintype "passive"))
    )
    (net (code "104") (name "Net-(U16-SD)") (class "Default")
      (node (ref "C145") (pin "1") (pinfunction "1_1") (pintype "passive"))
      (node (ref "U16") (pin "1") (pinfunction "SD_1") (pintype "passive"))
    )
    (net (code "105") (name "Net-(U17-RF_IN_1)") (class "Default")
      (node (ref "C145") (pin "2") (pinfunction "2_2") (pintype "passive"))
      (node (ref "R86") (pin "1") (pinfunction "1_1") (pintype "passive"))
      (node (ref "R90") (pin "1") (pinfunction "1_1") (pintype "passive"))
      (node (ref "U17") (pin "1") (pinfunction "RF_IN_1_1") (pintype "passive"))
    )
    (net (code "106") (name "Net-(U17-RF_IN_2)") (class "Default")
      (node (ref "C150") (pin "2") (pinfunction "2_2") (pintype "passive"))
      (node (ref "R91") (pin "2") (pinfunction "2_2") (pintype "passive"))
      (node (ref "R94") (pin "1") (pinfunction "1_1") (pintype "passive"))
      (node (ref "U17") (pin "4") (pinfunction "RF_IN_2_4") (pintype "passive"))
    )
    (net (code "107") (name "Net-(U17-RF_OUT_1)") (class "Default")
      (node (ref "C140") (pin "2") (pinfunction "2_2") (pintype "passive"))
      (node (ref "C141") (pin "2") (pinfunction "2_2") (pintype "passive"))
      (node (ref "L5") (pin "1") (pinfunction "1_1") (pintype "passive"))
      (node (ref "U17") (pin "8") (pinfunction "RF_OUT_1_8") (pintype "passive"))
    )
    (net (code "108") (name "Net-(U17-RF_OUT_2)") (class "Default")
      (node (ref "C148") (pin "2") (pinfunction "2_2") (pintype "passive"))
      (node (ref "C152") (pin "2") (pinfunction "2_2") (pintype "passive"))
      (node (ref "L6") (pin "2") (pinfunction "2_2") (pintype "passive"))
      (node (ref "U17") (pin "5") (pinfunction "RF_OUT_2_5") (pintype "passive"))
    )
    (net (code "109") (name "Net-(U18-P)") (class "Default")
      (node (ref "C142") (pin "2") (pinfunction "2_2") (pintype "passive"))
      (node (ref "U18") (pin "4") (pinfunction "P_4") (pintype "passive"))
    )
    (net (code "110") (name "Net-(U18-S)") (class "Default")
      (node (ref "C141") (pin "1") (pinfunction "1_1") (pintype "passive"))
      (node (ref "U18") (pin "3") (pinfunction "S_3") (pintype "passive"))
    )
    (net (code "111") (name "Net-(U18-SD)") (class "Default")
      (node (ref "C148") (pin "1") (pinfunction "1_1") (pintype "passive"))
      (node (ref "U18") (pin "1") (pinfunction "SD_1") (pintype "passive"))
    )
    (net (code "112") (name "Net-(U19-RF_IN)") (class "Default")
      (node (ref "C147") (pin "2") (pinfunction "2_2") (pintype "passive"))
      (node (ref "U19") (pin "3") (pinfunction "RF_IN_3") (pintype "passive"))
    )
    (net (code "113") (name "Net-(U19-RF_OUT)") (class "Default")
      (node (ref "C146") (pin "1") (pinfunction "1_1") (pintype "passive"))
      (node (ref "U19") (pin "4") (pinfunction "RF_OUT_4") (pintype "passive"))
    )
    (net (code "114") (name "unconnected-(U5-NC-Pad6)") (class "Default")
      (node (ref "U5") (pin "6") (pinfunction "NC_6") (pintype "passive"))
    )
    (net (code "115") (name "unconnected-(U12-NC-Pad2)") (class "Default")
      (node (ref "U12") (pin "2") (pinfunction "NC_2") (pintype "passive"))
    )
    (net (code "116") (name "unconnected-(U12-NC-Pad3)") (class "Default")
      (node (ref "U12") (pin "3") (pinfunction "NC_3") (pintype "passive"))
    )
    (net (code "117") (name "unconnected-(U14-LS-Pad1)") (class "Default")
      (node (ref "U14") (pin "1") (pinfunction "LS_1") (pintype "passive+no_connect"))
    )
    (net (code "118") (name "unconnected-(U15-NC-Pad2)") (class "Default")
      (node (ref "U15") (pin "2") (pinfunction "NC_2") (pintype "passive"))
    )
    (net (code "119") (name "unconnected-(U15-NC-Pad3)") (class "Default")
      (node (ref "U15") (pin "3") (pinfunction "NC_3") (pintype "passive"))
    )
    (net (code "120") (name "unconnected-(U16-NC-Pad2)") (class "Default")
      (node (ref "U16") (pin "2") (pinfunction "NC_2") (pintype "passive"))
    )
    (net (code "121") (name "unconnected-(U18-NC-Pad2)") (class "Default")
      (node (ref "U18") (pin "2") (pinfunction "NC_2") (pintype "passive"))
    )
    (net (code "122") (name "unconnected-(U19-NC-Pad6)") (class "Default")
      (node (ref "U19") (pin "6") (pinfunction "NC_6") (pintype "passive"))
    )
  )
)
